# main.net
KiCad netlist of a schematic drawn in EAGLE
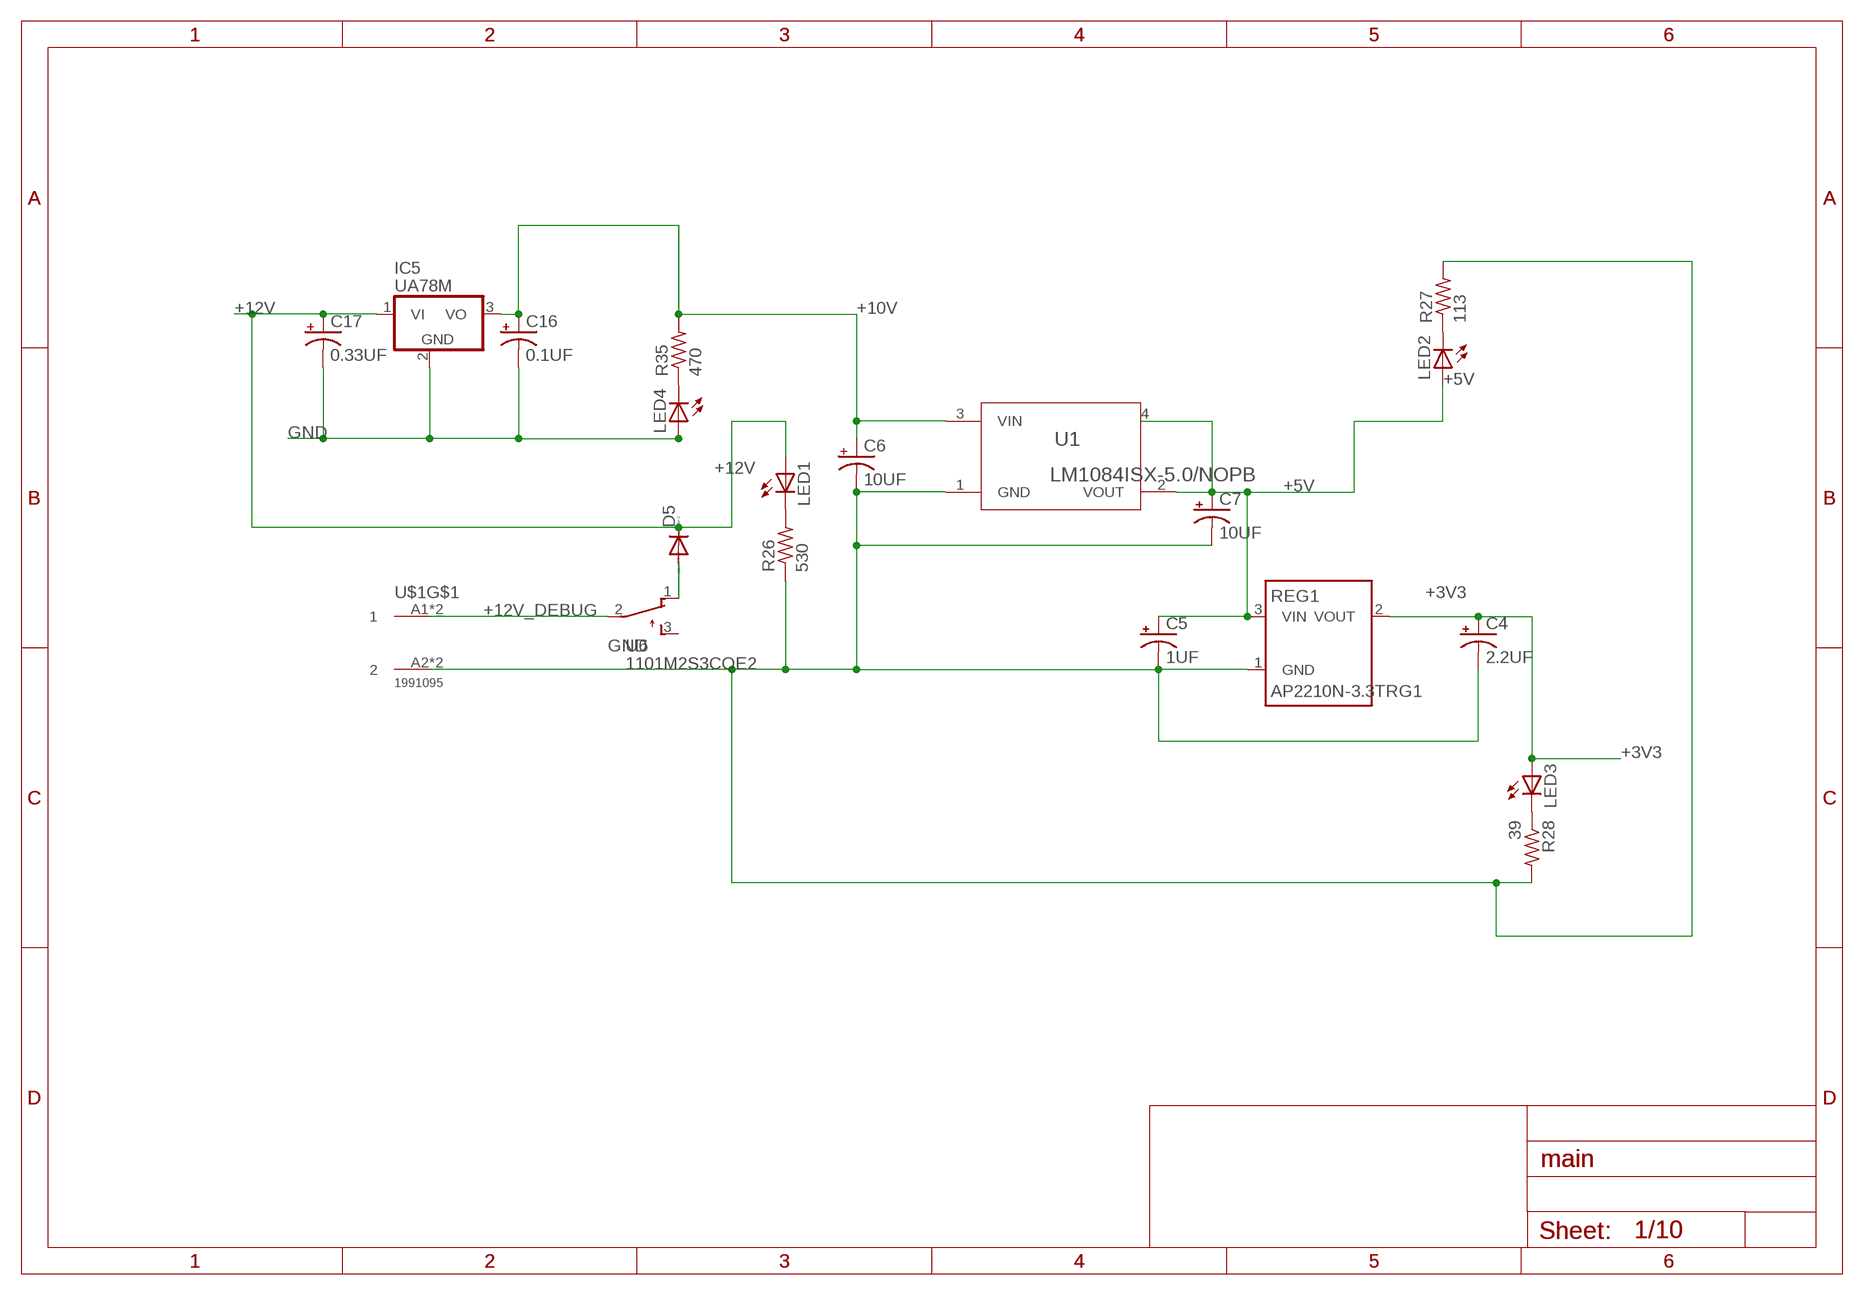
[diagram p0: schematic, sheet 1]
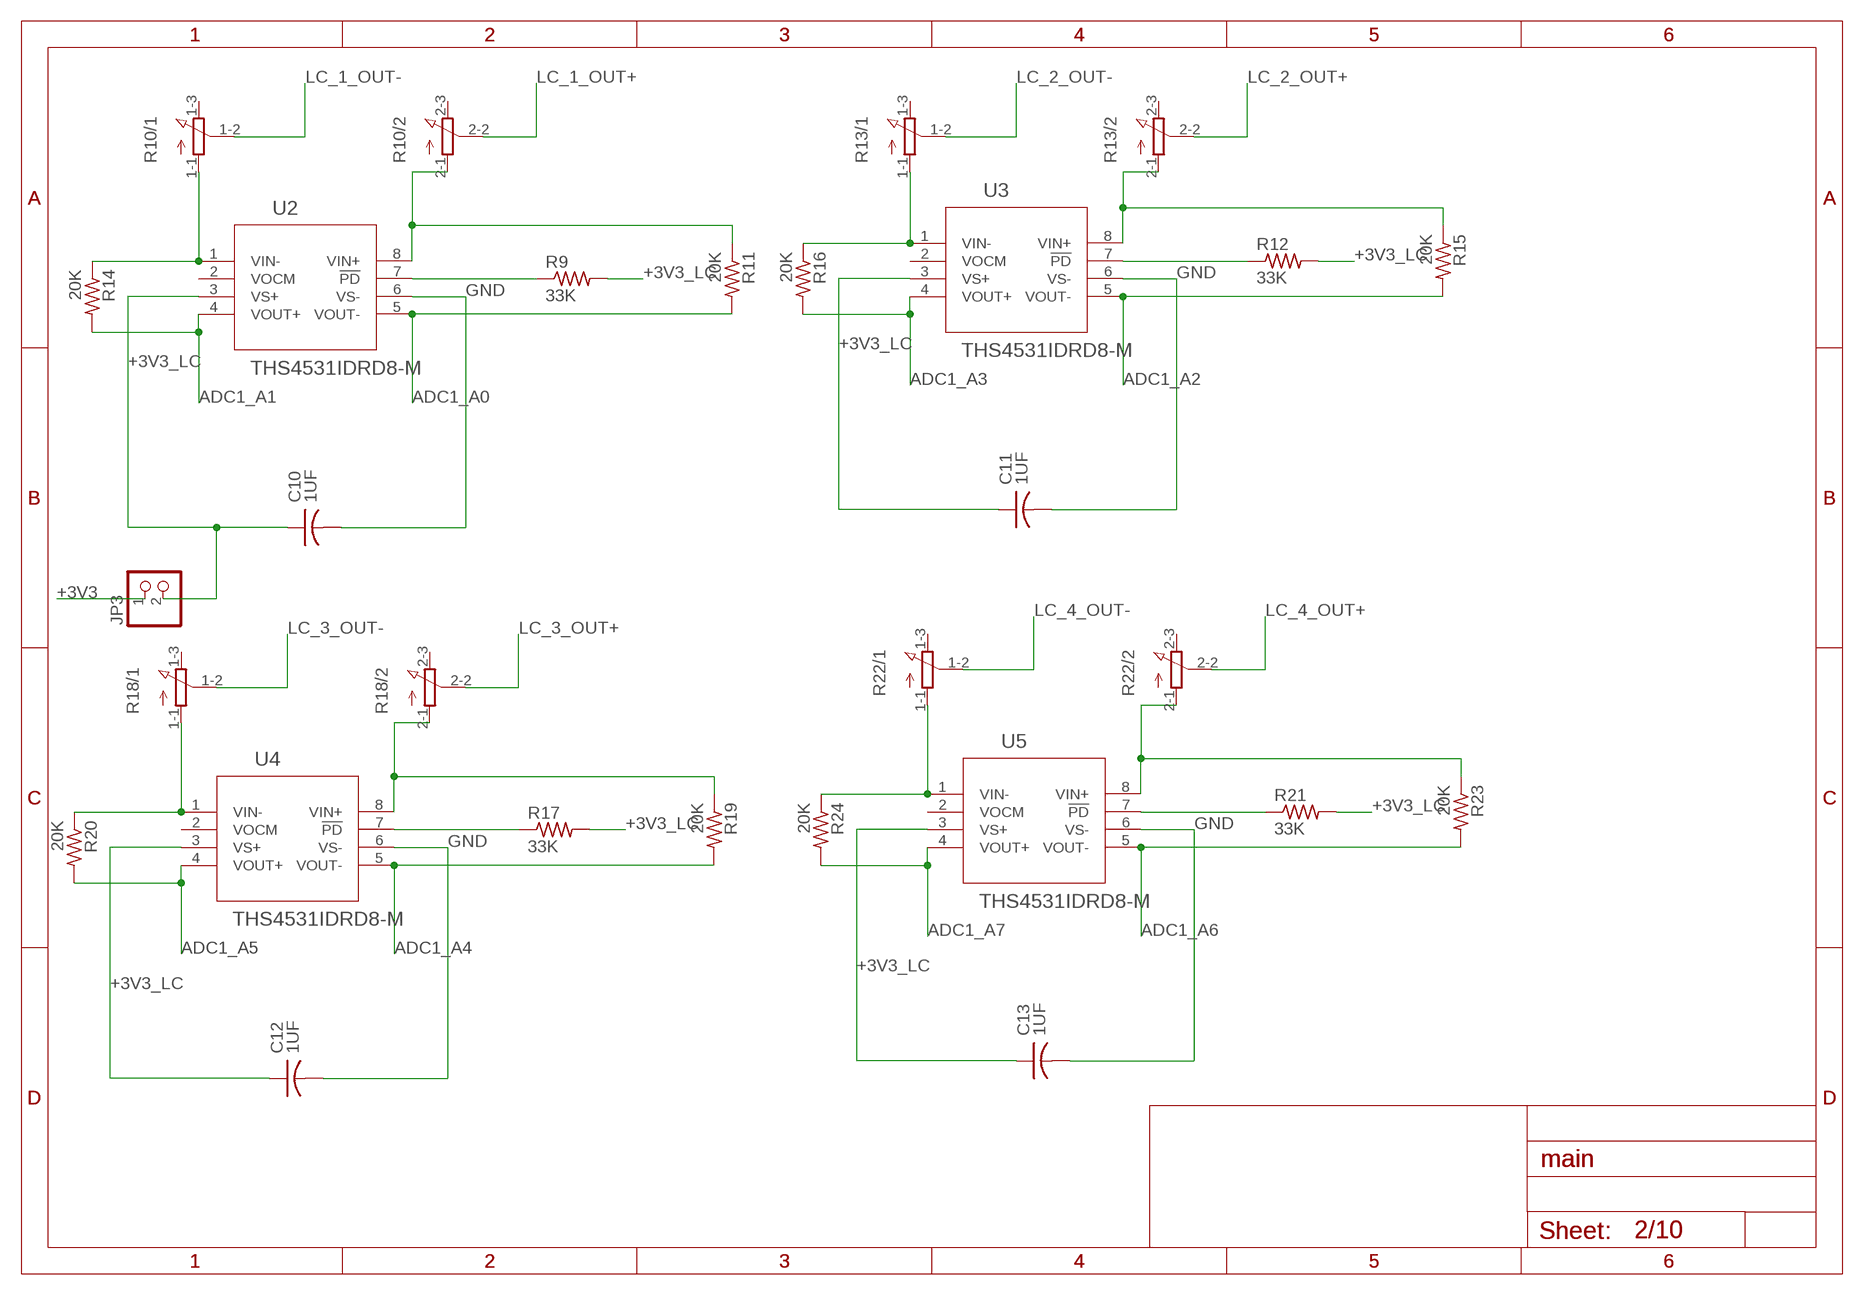
[diagram p1: schematic, sheet 2]
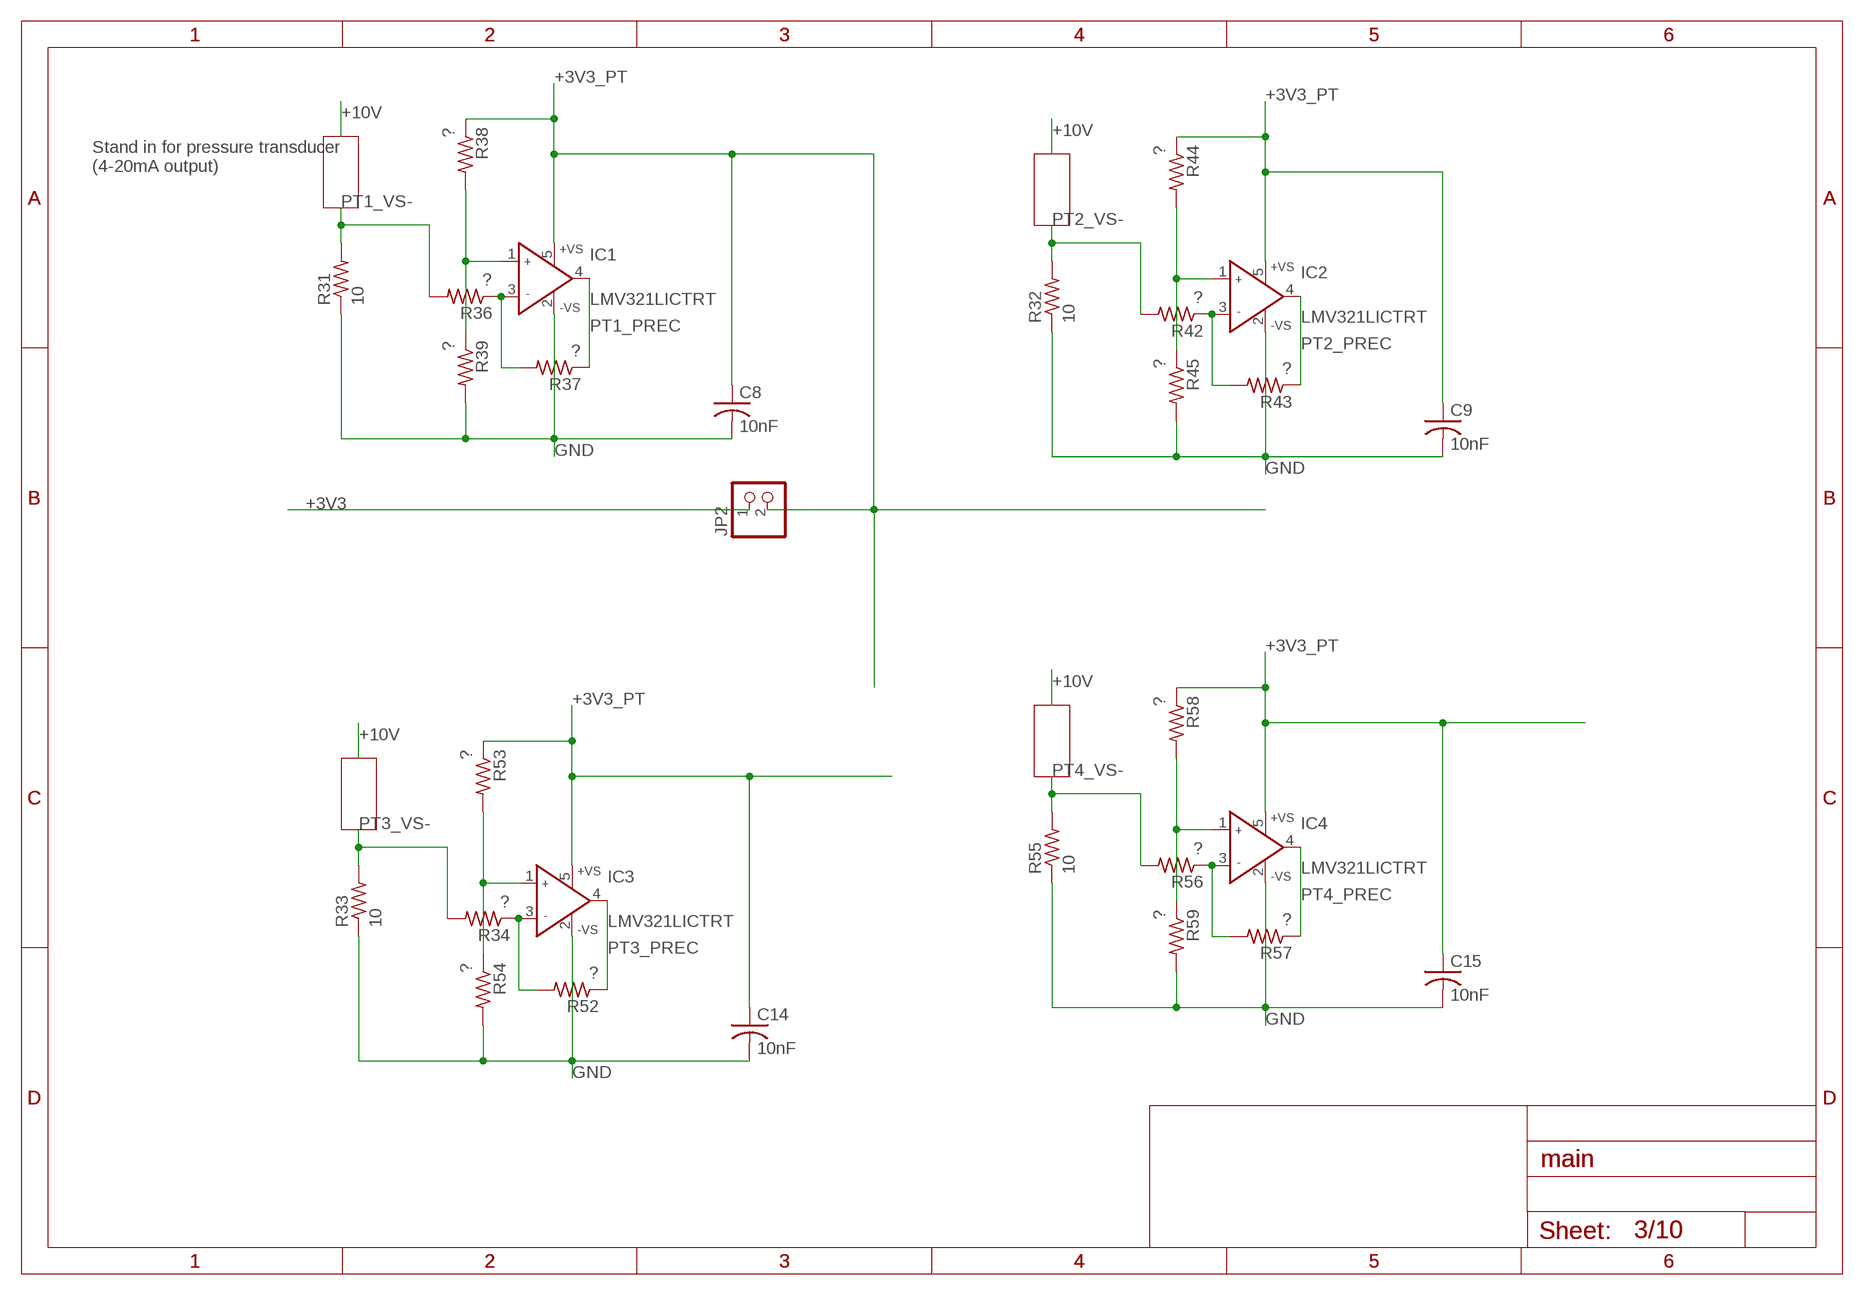
[diagram p2: schematic, sheet 3]
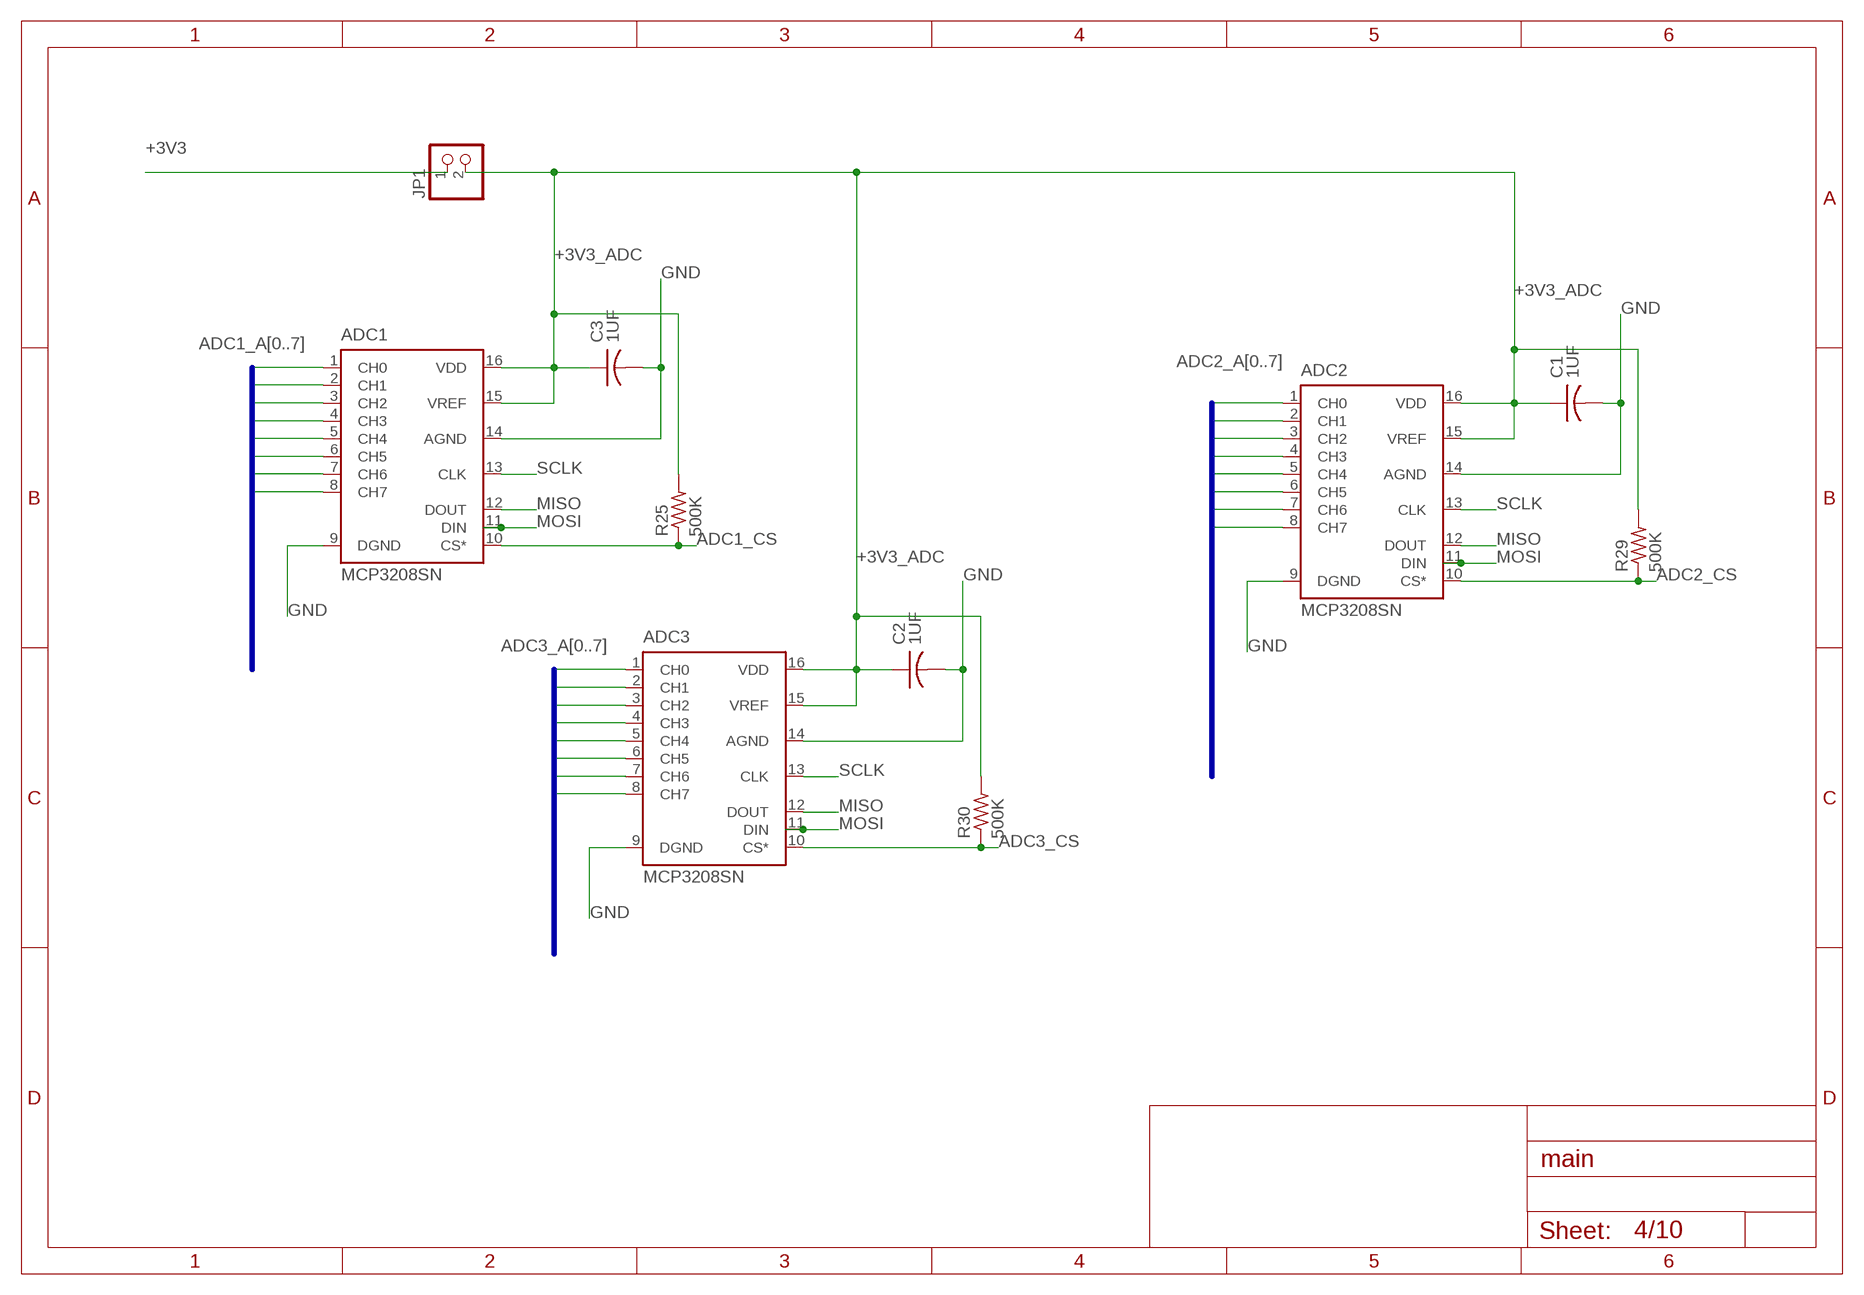
[diagram p3: schematic, sheet 4]
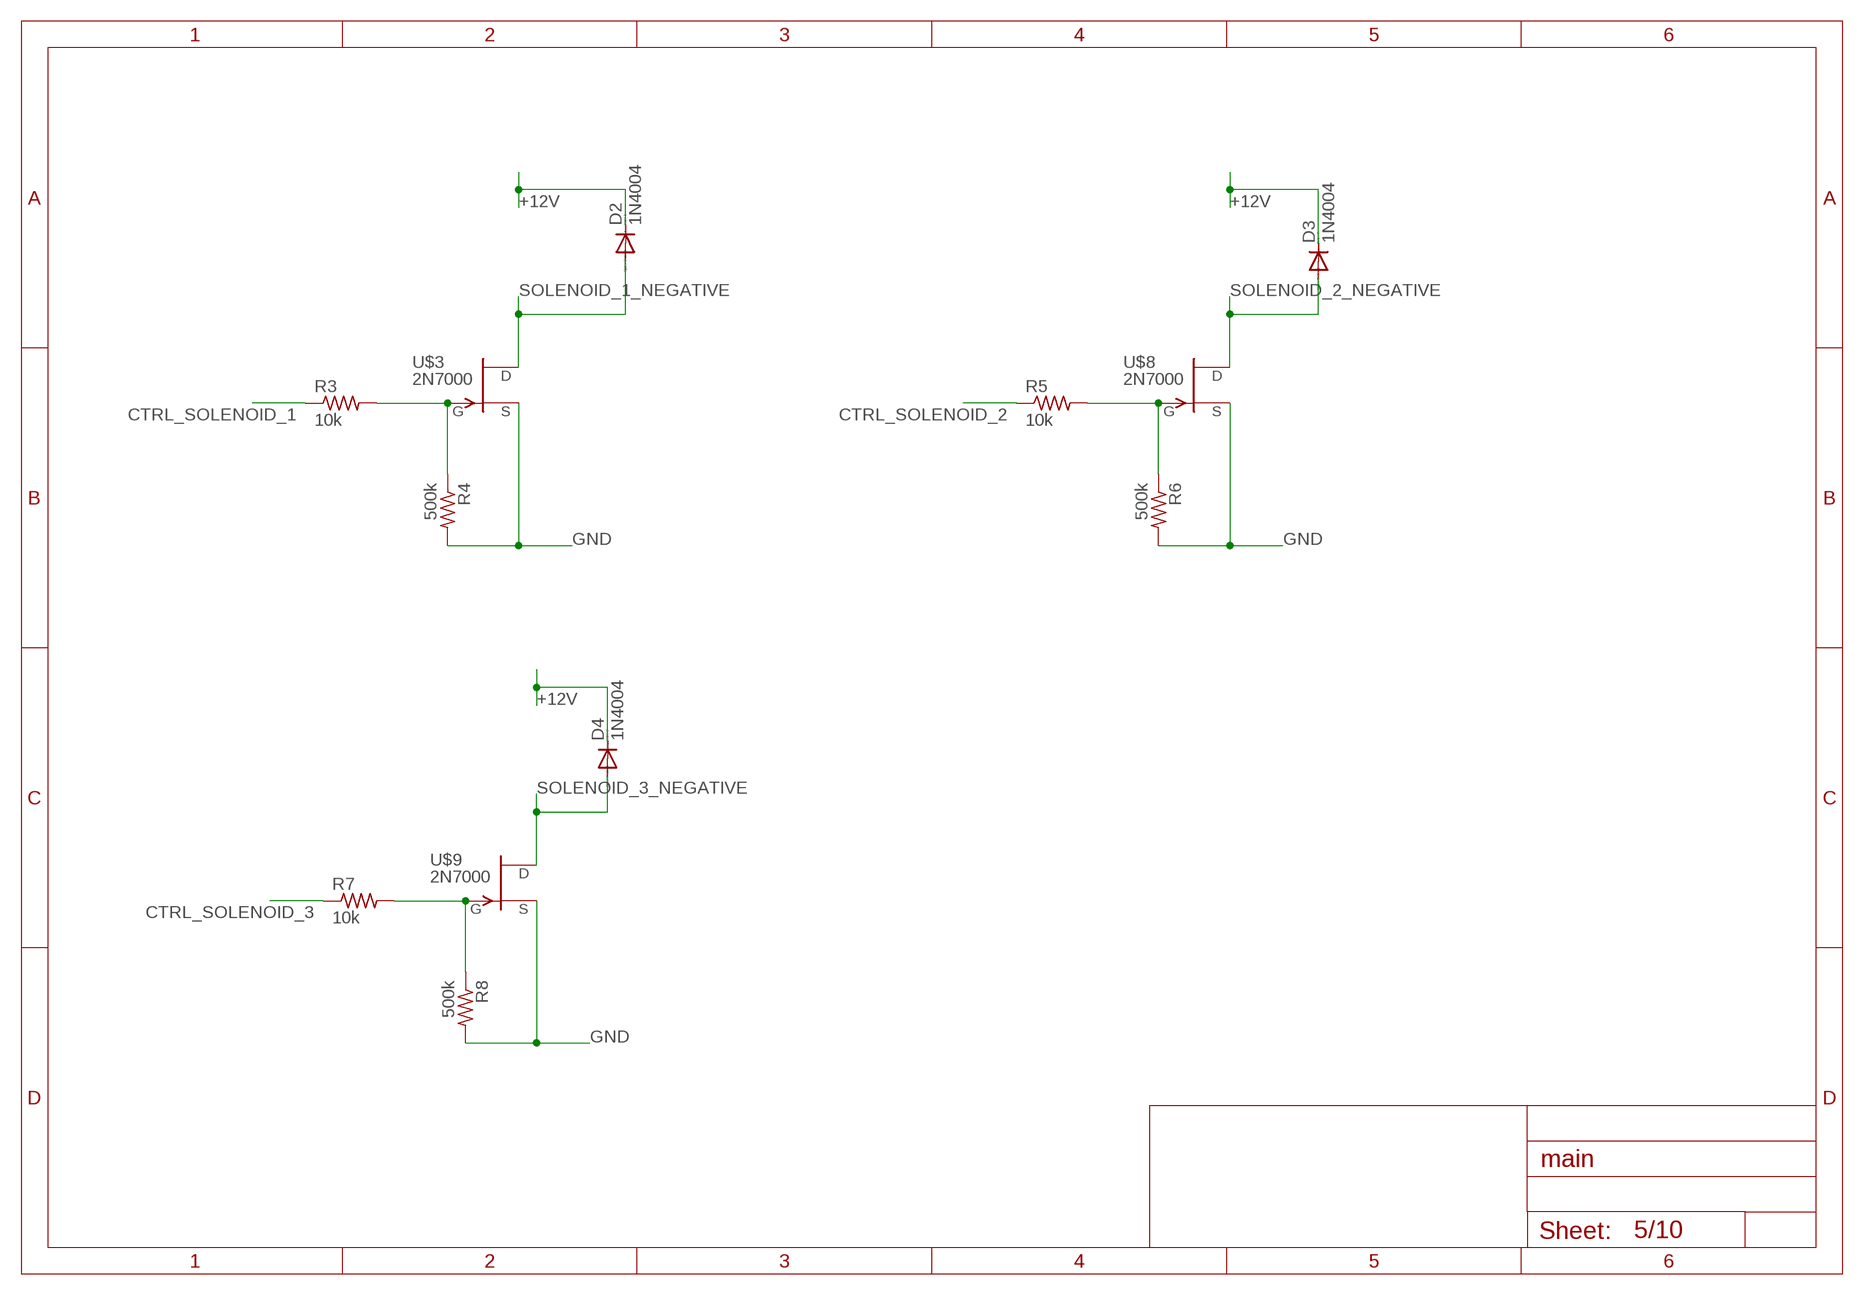
[diagram p4: schematic, sheet 5]
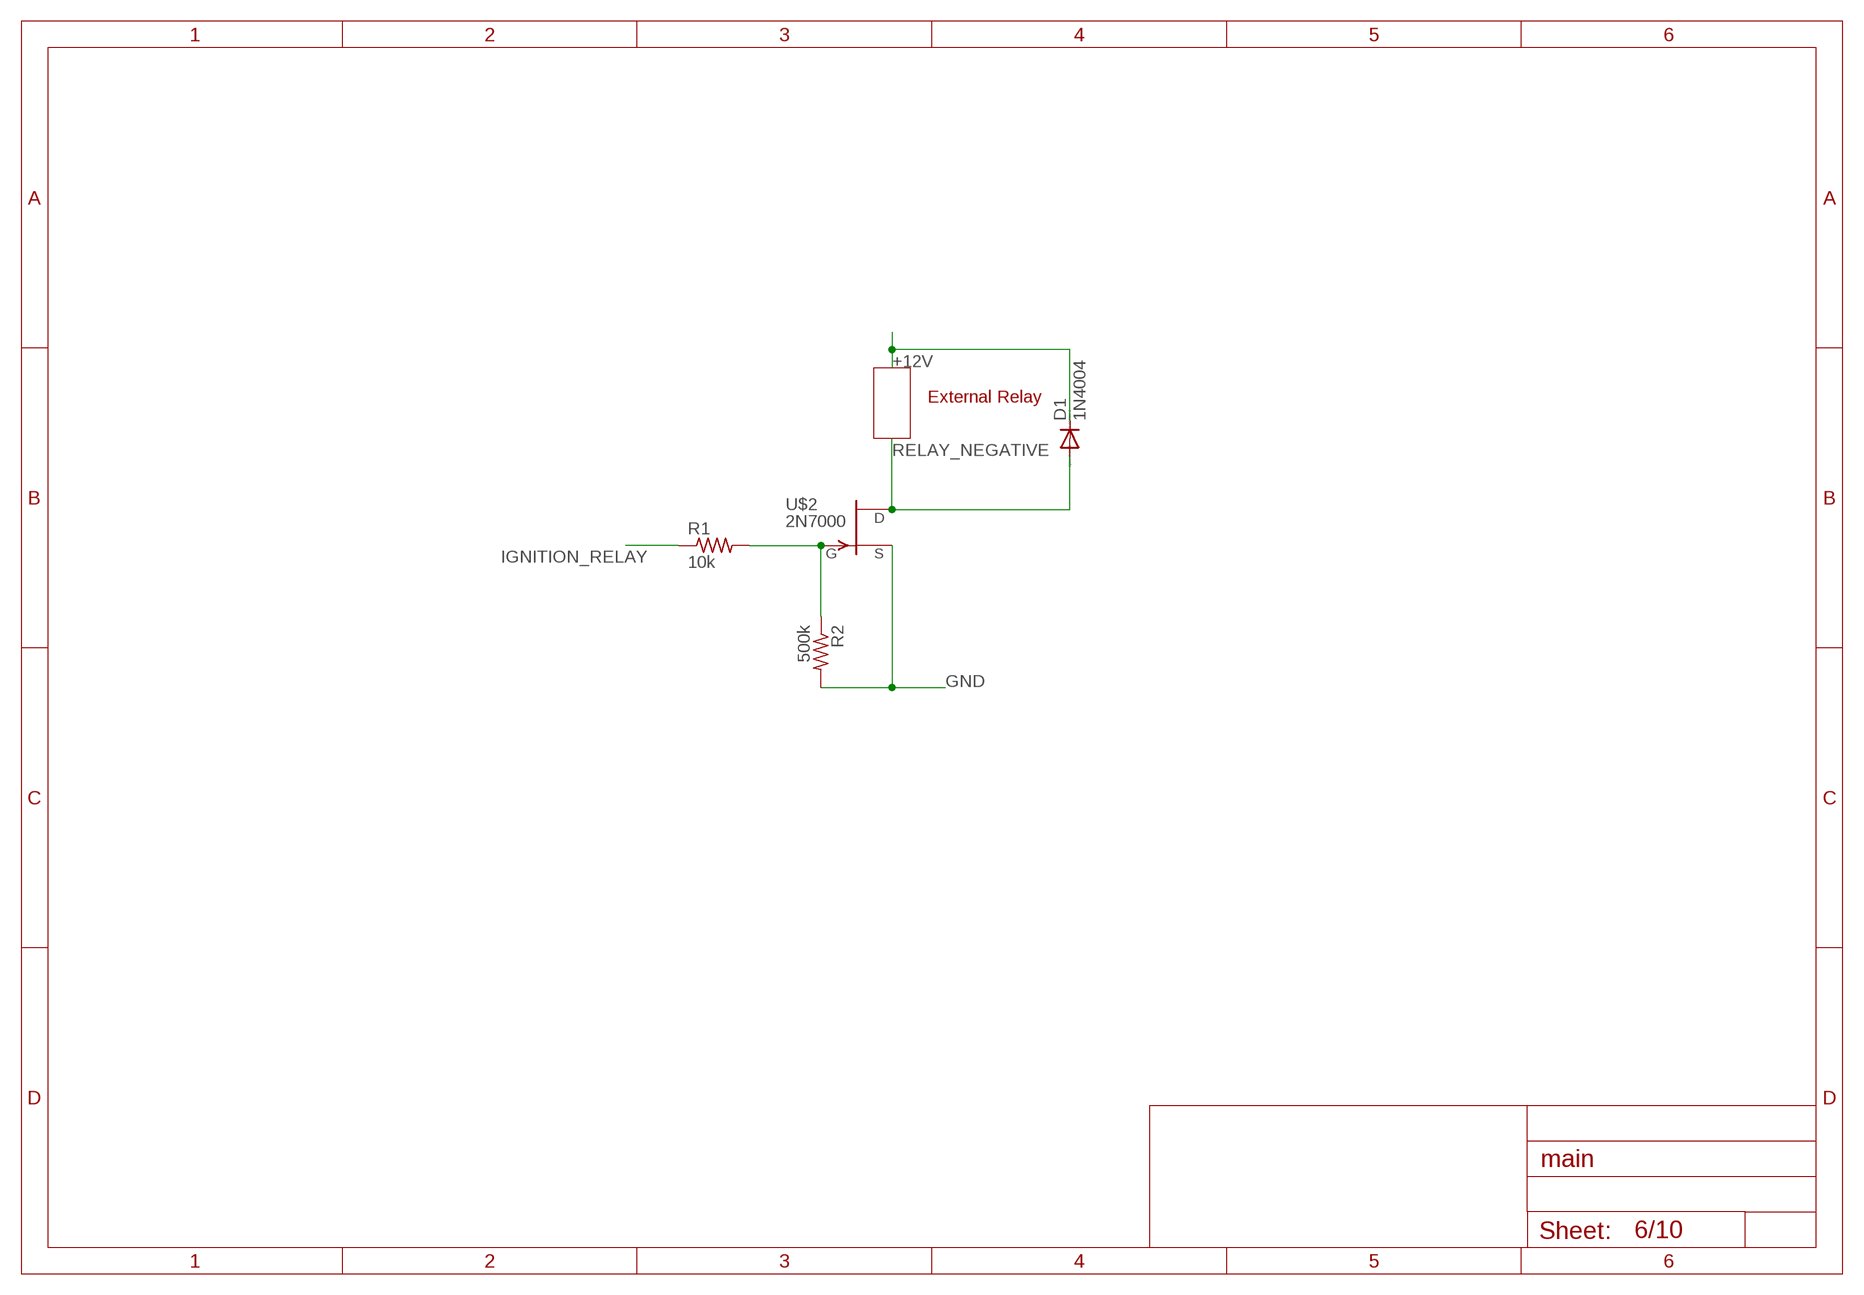
[diagram p5: schematic, sheet 6]
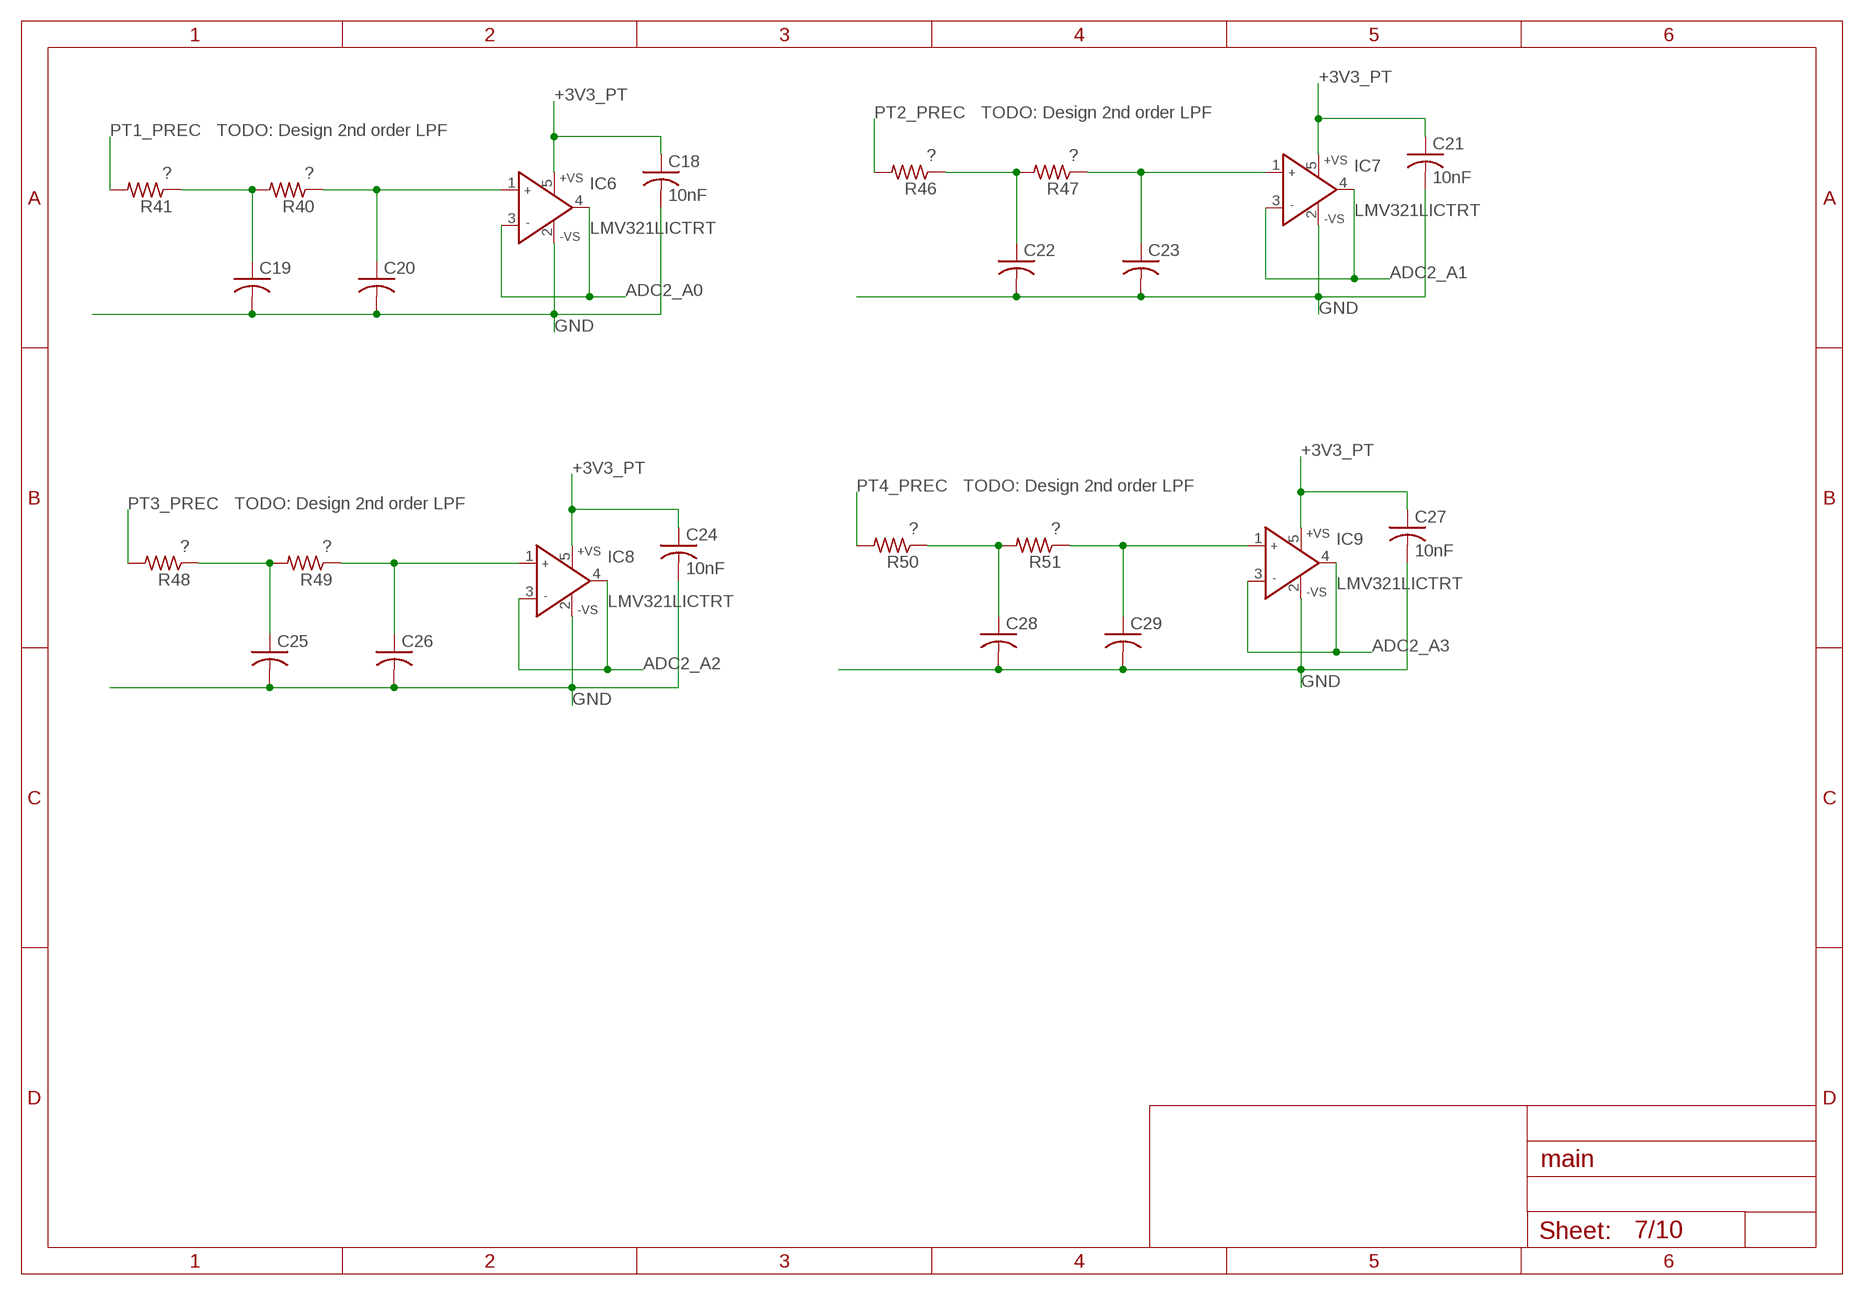
[diagram p6: schematic, sheet 7]
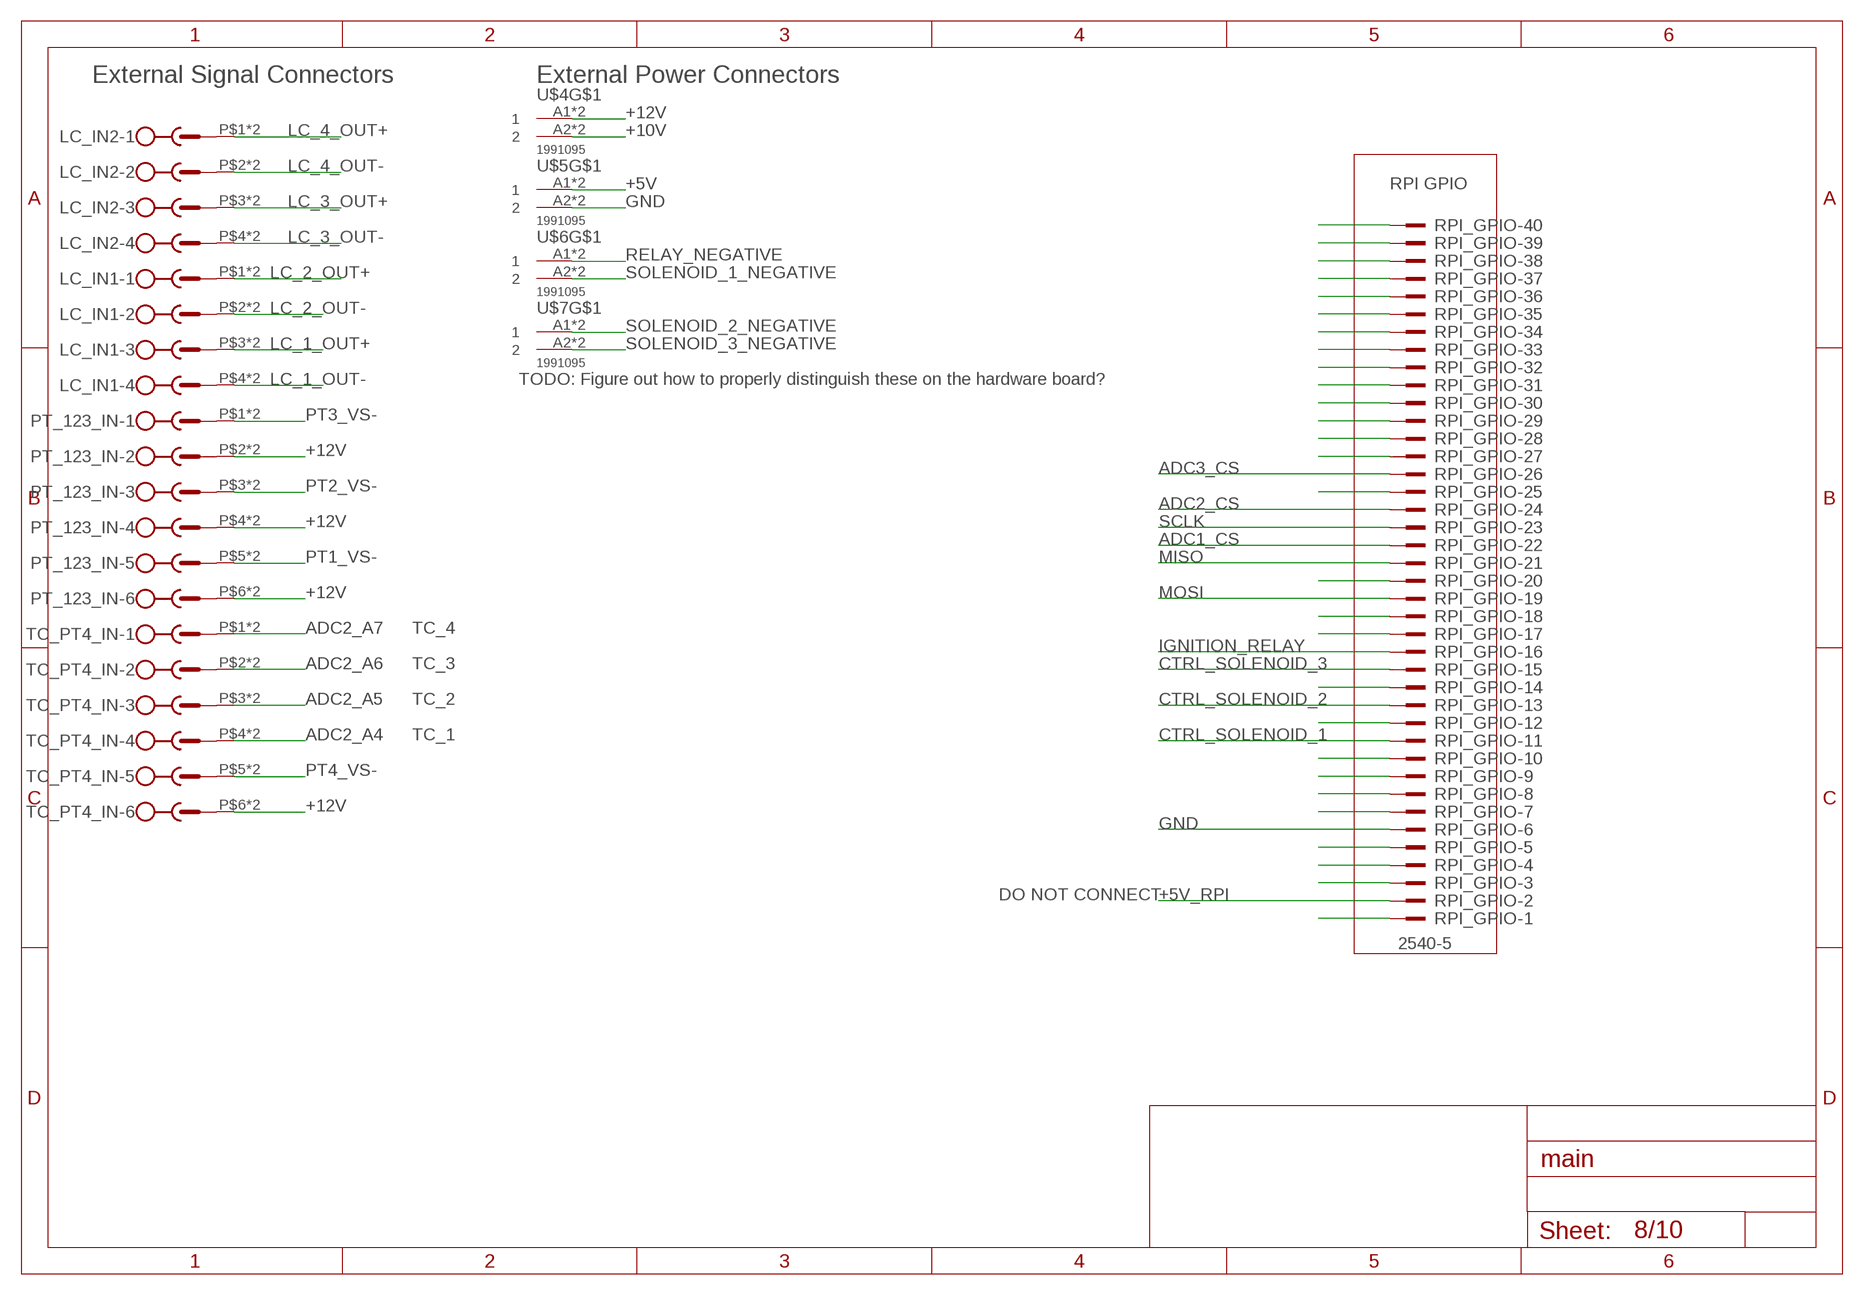
[diagram p7: schematic, sheet 8]
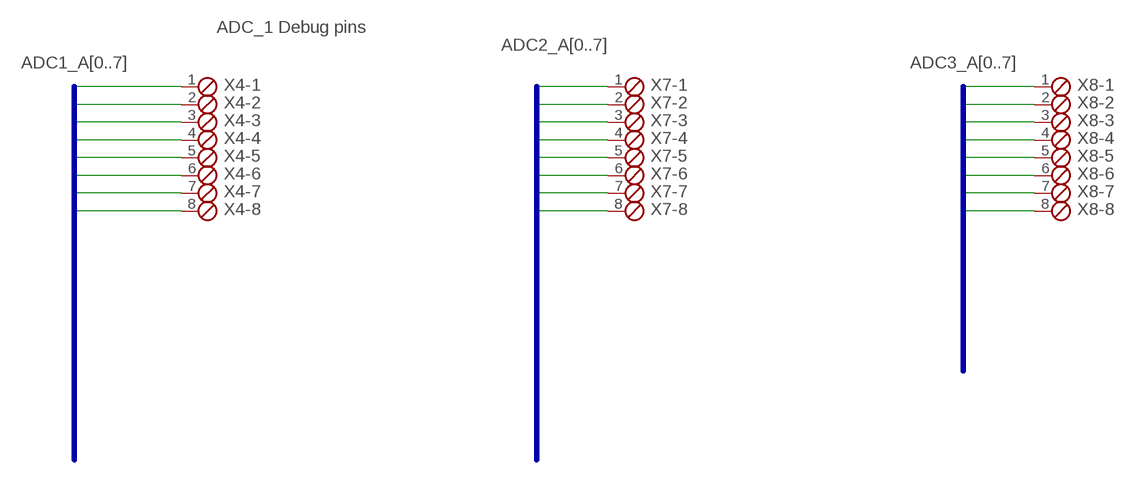
[diagram p8: schematic, sheet 9]

(export (version "E")
  (design (tool "Eeschema 10.0.6"))
  (components
    (comp (ref "C10")
      (value "1UF")
      (footprint "eagle-import:C0603")
      (libsource (lib "eagle-import") (part "C-USC0603"))
    )
    (comp (ref "C11")
      (value "1UF")
      (footprint "eagle-import:C0603")
      (libsource (lib "eagle-import") (part "C-USC0603"))
    )
    (comp (ref "C12")
      (value "1UF")
      (footprint "eagle-import:C0603")
      (libsource (lib "eagle-import") (part "C-USC0603"))
    )
    (comp (ref "C13")
      (value "1UF")
      (footprint "eagle-import:C0603")
      (libsource (lib "eagle-import") (part "C-USC0603"))
    )
    (comp (ref "JP3")
      (value "PINHD-1X2")
      (footprint "eagle-import:1X02")
      (libsource (lib "eagle-import") (part "PINHD-1X2"))
    )
    (comp (ref "R9")
      (value "33K")
      (footprint "eagle-import:R0603")
      (libsource (lib "eagle-import") (part "R-US_R0603"))
    )
    (comp (ref "R10")
      (value "PTD902")
      (footprint "eagle-import:PTD902")
      (libsource (lib "eagle-import") (part "PTD902"))
    )
    (comp (ref "R11")
      (value "20K")
      (footprint "eagle-import:R0603")
      (libsource (lib "eagle-import") (part "R-US_R0603"))
    )
    (comp (ref "R12")
      (value "33K")
      (footprint "eagle-import:R0603")
      (libsource (lib "eagle-import") (part "R-US_R0603"))
    )
    (comp (ref "R13")
      (value "PTD902")
      (footprint "eagle-import:PTD902")
      (libsource (lib "eagle-import") (part "PTD902"))
    )
    (comp (ref "R14")
      (value "20K")
      (footprint "eagle-import:R0603")
      (libsource (lib "eagle-import") (part "R-US_R0603"))
    )
    (comp (ref "R15")
      (value "20K")
      (footprint "eagle-import:R0603")
      (libsource (lib "eagle-import") (part "R-US_R0603"))
    )
    (comp (ref "R16")
      (value "20K")
      (footprint "eagle-import:R0603")
      (libsource (lib "eagle-import") (part "R-US_R0603"))
    )
    (comp (ref "R17")
      (value "33K")
      (footprint "eagle-import:R0603")
      (libsource (lib "eagle-import") (part "R-US_R0603"))
    )
    (comp (ref "R18")
      (value "PTD902")
      (footprint "eagle-import:PTD902")
      (libsource (lib "eagle-import") (part "PTD902"))
    )
    (comp (ref "R19")
      (value "20K")
      (footprint "eagle-import:R0603")
      (libsource (lib "eagle-import") (part "R-US_R0603"))
    )
    (comp (ref "R20")
      (value "20K")
      (footprint "eagle-import:R0603")
      (libsource (lib "eagle-import") (part "R-US_R0603"))
    )
    (comp (ref "R21")
      (value "33K")
      (footprint "eagle-import:R0603")
      (libsource (lib "eagle-import") (part "R-US_R0603"))
    )
    (comp (ref "R22")
      (value "PTD902")
      (footprint "eagle-import:PTD902")
      (libsource (lib "eagle-import") (part "PTD902"))
    )
    (comp (ref "R23")
      (value "20K")
      (footprint "eagle-import:R0603")
      (libsource (lib "eagle-import") (part "R-US_R0603"))
    )
    (comp (ref "R24")
      (value "20K")
      (footprint "eagle-import:R0603")
      (libsource (lib "eagle-import") (part "R-US_R0603"))
    )
    (comp (ref "U2")
      (value "THS4531IDRD8-M")
      (footprint "eagle-import:D8-M")
      (fields (field (name "MANUFACTURER_PART_NUMBER") "THS4531IDR"))
      (libsource (lib "eagle-import") (part "THS4531IDRD8-M"))
    )
    (comp (ref "U3")
      (value "THS4531IDRD8-M")
      (footprint "eagle-import:D8-M")
      (fields (field (name "MANUFACTURER_PART_NUMBER") "THS4531IDR"))
      (libsource (lib "eagle-import") (part "THS4531IDRD8-M"))
    )
    (comp (ref "U4")
      (value "THS4531IDRD8-M")
      (footprint "eagle-import:D8-M")
      (fields (field (name "MANUFACTURER_PART_NUMBER") "THS4531IDR"))
      (libsource (lib "eagle-import") (part "THS4531IDRD8-M"))
    )
    (comp (ref "U5")
      (value "THS4531IDRD8-M")
      (footprint "eagle-import:D8-M")
      (fields (field (name "MANUFACTURER_PART_NUMBER") "THS4531IDR"))
      (libsource (lib "eagle-import") (part "THS4531IDRD8-M"))
    )
    (comp (ref "D2")
      (value "1N4004")
      (footprint "eagle-import:DO41-10")
      (libsource (lib "eagle-import") (part "1N4004"))
    )
    (comp (ref "D3")
      (value "1N4004")
      (footprint "eagle-import:DO41-10")
      (libsource (lib "eagle-import") (part "1N4004"))
    )
    (comp (ref "D4")
      (value "1N4004")
      (footprint "eagle-import:DO41-10")
      (libsource (lib "eagle-import") (part "1N4004"))
    )
    (comp (ref "R3")
      (value "10k")
      (footprint "eagle-import:R0603")
      (libsource (lib "eagle-import") (part "R-US_R0603"))
    )
    (comp (ref "R4")
      (value "500k")
      (footprint "eagle-import:R0603")
      (libsource (lib "eagle-import") (part "R-US_R0603"))
    )
    (comp (ref "R5")
      (value "10k")
      (footprint "eagle-import:R0603")
      (libsource (lib "eagle-import") (part "R-US_R0603"))
    )
    (comp (ref "R6")
      (value "500k")
      (footprint "eagle-import:R0603")
      (libsource (lib "eagle-import") (part "R-US_R0603"))
    )
    (comp (ref "R7")
      (value "10k")
      (footprint "eagle-import:R0603")
      (libsource (lib "eagle-import") (part "R-US_R0603"))
    )
    (comp (ref "R8")
      (value "500k")
      (footprint "eagle-import:R0603")
      (libsource (lib "eagle-import") (part "R-US_R0603"))
    )
    (comp (ref "U$3")
      (value "2N7000")
      (footprint "eagle-import:SOT23")
      (libsource (lib "eagle-import") (part "2N7000"))
    )
    (comp (ref "U$8")
      (value "2N7000")
      (footprint "eagle-import:SOT23")
      (libsource (lib "eagle-import") (part "2N7000"))
    )
    (comp (ref "U$9")
      (value "2N7000")
      (footprint "eagle-import:SOT23")
      (libsource (lib "eagle-import") (part "2N7000"))
    )
    (comp (ref "D1")
      (value "1N4004")
      (footprint "eagle-import:DO41-10")
      (libsource (lib "eagle-import") (part "1N4004"))
    )
    (comp (ref "R1")
      (value "10k")
      (footprint "eagle-import:R0603")
      (libsource (lib "eagle-import") (part "R-US_R0603"))
    )
    (comp (ref "R2")
      (value "500k")
      (footprint "eagle-import:R0603")
      (libsource (lib "eagle-import") (part "R-US_R0603"))
    )
    (comp (ref "U$2")
      (value "2N7000")
      (footprint "eagle-import:SOT23")
      (libsource (lib "eagle-import") (part "2N7000"))
    )
    (comp (ref "X4")
      (value "MPT8")
      (footprint "eagle-import:8POL254")
      (libsource (lib "eagle-import") (part "MPT8"))
    )
    (comp (ref "X7")
      (value "MPT8")
      (footprint "eagle-import:8POL254")
      (libsource (lib "eagle-import") (part "MPT8"))
    )
    (comp (ref "X8")
      (value "MPT8")
      (footprint "eagle-import:8POL254")
      (libsource (lib "eagle-import") (part "MPT8"))
    )
    (comp (ref "LC_IN1")
      (value "1770908")
      (footprint "eagle-import:1770908")
      (libsource (lib "eagle-import") (part "1770908"))
    )
    (comp (ref "LC_IN2")
      (value "1770908")
      (footprint "eagle-import:1770908")
      (libsource (lib "eagle-import") (part "1770908"))
    )
    (comp (ref "PT_123_IN")
      (value "1770924")
      (footprint "eagle-import:1770924")
      (libsource (lib "eagle-import") (part "1770924"))
    )
    (comp (ref "RPI_GPIO")
      (value "2540-5")
      (footprint "eagle-import:PAK100_2500-5-40")
      (libsource (lib "eagle-import") (part "2540-5"))
    )
    (comp (ref "TC_PT4_IN")
      (value "1770924")
      (footprint "eagle-import:1770924")
      (libsource (lib "eagle-import") (part "1770924"))
    )
    (comp (ref "U$4")
      (value "1991095")
      (footprint "eagle-import:1991095")
      (libsource (lib "eagle-import") (part "1991095"))
    )
    (comp (ref "U$5")
      (value "1991095")
      (footprint "eagle-import:1991095")
      (libsource (lib "eagle-import") (part "1991095"))
    )
    (comp (ref "U$6")
      (value "1991095")
      (footprint "eagle-import:1991095")
      (libsource (lib "eagle-import") (part "1991095"))
    )
    (comp (ref "U$7")
      (value "1991095")
      (footprint "eagle-import:1991095")
      (libsource (lib "eagle-import") (part "1991095"))
    )
    (comp (ref "C18")
      (value "10nF")
      (footprint "eagle-import:C0402K")
      (libsource (lib "eagle-import") (part "C-USC0402K"))
    )
    (comp (ref "C19")
      (value "C-US025-025X050")
      (footprint "eagle-import:C025-025X050")
      (libsource (lib "eagle-import") (part "C-US025-025X050"))
    )
    (comp (ref "C20")
      (value "C-US025-025X050")
      (footprint "eagle-import:C025-025X050")
      (libsource (lib "eagle-import") (part "C-US025-025X050"))
    )
    (comp (ref "C21")
      (value "10nF")
      (footprint "eagle-import:C0402K")
      (libsource (lib "eagle-import") (part "C-USC0402K"))
    )
    (comp (ref "C22")
      (value "C-US025-025X050")
      (footprint "eagle-import:C025-025X050")
      (libsource (lib "eagle-import") (part "C-US025-025X050"))
    )
    (comp (ref "C23")
      (value "C-US025-025X050")
      (footprint "eagle-import:C025-025X050")
      (libsource (lib "eagle-import") (part "C-US025-025X050"))
    )
    (comp (ref "C24")
      (value "10nF")
      (footprint "eagle-import:C0402K")
      (libsource (lib "eagle-import") (part "C-USC0402K"))
    )
    (comp (ref "C25")
      (value "C-US025-025X050")
      (footprint "eagle-import:C025-025X050")
      (libsource (lib "eagle-import") (part "C-US025-025X050"))
    )
    (comp (ref "C26")
      (value "C-US025-025X050")
      (footprint "eagle-import:C025-025X050")
      (libsource (lib "eagle-import") (part "C-US025-025X050"))
    )
    (comp (ref "C27")
      (value "10nF")
      (footprint "eagle-import:C0402K")
      (libsource (lib "eagle-import") (part "C-USC0402K"))
    )
    (comp (ref "C28")
      (value "C-US025-025X050")
      (footprint "eagle-import:C025-025X050")
      (libsource (lib "eagle-import") (part "C-US025-025X050"))
    )
    (comp (ref "C29")
      (value "C-US025-025X050")
      (footprint "eagle-import:C025-025X050")
      (libsource (lib "eagle-import") (part "C-US025-025X050"))
    )
    (comp (ref "IC6")
      (value "LMV321LICTRT")
      (footprint "eagle-import:SOT23-5")
      (fields (field (name "MF") "ALTERA CORPORATION") (field (name "MPN") "AD8065ARTZ-REEL7"))
      (libsource (lib "eagle-import") (part "LMV321LICTRT"))
    )
    (comp (ref "IC7")
      (value "LMV321LICTRT")
      (footprint "eagle-import:SOT23-5")
      (fields (field (name "MF") "ALTERA CORPORATION") (field (name "MPN") "AD8065ARTZ-REEL7"))
      (libsource (lib "eagle-import") (part "LMV321LICTRT"))
    )
    (comp (ref "IC8")
      (value "LMV321LICTRT")
      (footprint "eagle-import:SOT23-5")
      (fields (field (name "MF") "ALTERA CORPORATION") (field (name "MPN") "AD8065ARTZ-REEL7"))
      (libsource (lib "eagle-import") (part "LMV321LICTRT"))
    )
    (comp (ref "IC9")
      (value "LMV321LICTRT")
      (footprint "eagle-import:SOT23-5")
      (fields (field (name "MF") "ALTERA CORPORATION") (field (name "MPN") "AD8065ARTZ-REEL7"))
      (libsource (lib "eagle-import") (part "LMV321LICTRT"))
    )
    (comp (ref "R40")
      (value "?")
      (footprint "eagle-import:0204_7")
      (libsource (lib "eagle-import") (part "R-US_0204/7"))
    )
    (comp (ref "R41")
      (value "?")
      (footprint "eagle-import:0204_7")
      (libsource (lib "eagle-import") (part "R-US_0204/7"))
    )
    (comp (ref "R46")
      (value "?")
      (footprint "eagle-import:0204_7")
      (libsource (lib "eagle-import") (part "R-US_0204/7"))
    )
    (comp (ref "R47")
      (value "?")
      (footprint "eagle-import:0204_7")
      (libsource (lib "eagle-import") (part "R-US_0204/7"))
    )
    (comp (ref "R48")
      (value "?")
      (footprint "eagle-import:0204_7")
      (libsource (lib "eagle-import") (part "R-US_0204/7"))
    )
    (comp (ref "R49")
      (value "?")
      (footprint "eagle-import:0204_7")
      (libsource (lib "eagle-import") (part "R-US_0204/7"))
    )
    (comp (ref "R50")
      (value "?")
      (footprint "eagle-import:0204_7")
      (libsource (lib "eagle-import") (part "R-US_0204/7"))
    )
    (comp (ref "R51")
      (value "?")
      (footprint "eagle-import:0204_7")
      (libsource (lib "eagle-import") (part "R-US_0204/7"))
    )
    (comp (ref "C8")
      (value "10nF")
      (footprint "eagle-import:C0402K")
      (libsource (lib "eagle-import") (part "C-USC0402K"))
    )
    (comp (ref "C9")
      (value "10nF")
      (footprint "eagle-import:C0402K")
      (libsource (lib "eagle-import") (part "C-USC0402K"))
    )
    (comp (ref "C14")
      (value "10nF")
      (footprint "eagle-import:C0402K")
      (libsource (lib "eagle-import") (part "C-USC0402K"))
    )
    (comp (ref "C15")
      (value "10nF")
      (footprint "eagle-import:C0402K")
      (libsource (lib "eagle-import") (part "C-USC0402K"))
    )
    (comp (ref "IC1")
      (value "LMV321LICTRT")
      (footprint "eagle-import:SOT23-5")
      (fields (field (name "MF") "ALTERA CORPORATION") (field (name "MPN") "AD8065ARTZ-REEL7"))
      (libsource (lib "eagle-import") (part "LMV321LICTRT"))
    )
    (comp (ref "IC2")
      (value "LMV321LICTRT")
      (footprint "eagle-import:SOT23-5")
      (fields (field (name "MF") "ALTERA CORPORATION") (field (name "MPN") "AD8065ARTZ-REEL7"))
      (libsource (lib "eagle-import") (part "LMV321LICTRT"))
    )
    (comp (ref "IC3")
      (value "LMV321LICTRT")
      (footprint "eagle-import:SOT23-5")
      (fields (field (name "MF") "ALTERA CORPORATION") (field (name "MPN") "AD8065ARTZ-REEL7"))
      (libsource (lib "eagle-import") (part "LMV321LICTRT"))
    )
    (comp (ref "IC4")
      (value "LMV321LICTRT")
      (footprint "eagle-import:SOT23-5")
      (fields (field (name "MF") "ALTERA CORPORATION") (field (name "MPN") "AD8065ARTZ-REEL7"))
      (libsource (lib "eagle-import") (part "LMV321LICTRT"))
    )
    (comp (ref "JP2")
      (value "PINHD-1X2")
      (footprint "eagle-import:1X02")
      (libsource (lib "eagle-import") (part "PINHD-1X2"))
    )
    (comp (ref "R31")
      (value "10")
      (footprint "eagle-import:R0603")
      (libsource (lib "eagle-import") (part "R-US_R0603"))
    )
    (comp (ref "R32")
      (value "10")
      (footprint "eagle-import:R0603")
      (libsource (lib "eagle-import") (part "R-US_R0603"))
    )
    (comp (ref "R33")
      (value "10")
      (footprint "eagle-import:R0603")
      (libsource (lib "eagle-import") (part "R-US_R0603"))
    )
    (comp (ref "R34")
      (value "?")
      (footprint "eagle-import:0204_7")
      (libsource (lib "eagle-import") (part "R-US_0204/7"))
    )
    (comp (ref "R36")
      (value "?")
      (footprint "eagle-import:0204_7")
      (libsource (lib "eagle-import") (part "R-US_0204/7"))
    )
    (comp (ref "R37")
      (value "?")
      (footprint "eagle-import:0204_7")
      (libsource (lib "eagle-import") (part "R-US_0204/7"))
    )
    (comp (ref "R38")
      (value "?")
      (footprint "eagle-import:0204_7")
      (libsource (lib "eagle-import") (part "R-US_0204/7"))
    )
    (comp (ref "R39")
      (value "?")
      (footprint "eagle-import:0204_7")
      (libsource (lib "eagle-import") (part "R-US_0204/7"))
    )
    (comp (ref "R42")
      (value "?")
      (footprint "eagle-import:0204_7")
      (libsource (lib "eagle-import") (part "R-US_0204/7"))
    )
    (comp (ref "R43")
      (value "?")
      (footprint "eagle-import:0204_7")
      (libsource (lib "eagle-import") (part "R-US_0204/7"))
    )
    (comp (ref "R44")
      (value "?")
      (footprint "eagle-import:0204_7")
      (libsource (lib "eagle-import") (part "R-US_0204/7"))
    )
    (comp (ref "R45")
      (value "?")
      (footprint "eagle-import:0204_7")
      (libsource (lib "eagle-import") (part "R-US_0204/7"))
    )
    (comp (ref "R52")
      (value "?")
      (footprint "eagle-import:0204_7")
      (libsource (lib "eagle-import") (part "R-US_0204/7"))
    )
    (comp (ref "R53")
      (value "?")
      (footprint "eagle-import:0204_7")
      (libsource (lib "eagle-import") (part "R-US_0204/7"))
    )
    (comp (ref "R54")
      (value "?")
      (footprint "eagle-import:0204_7")
      (libsource (lib "eagle-import") (part "R-US_0204/7"))
    )
    (comp (ref "R55")
      (value "10")
      (footprint "eagle-import:R0603")
      (libsource (lib "eagle-import") (part "R-US_R0603"))
    )
    (comp (ref "R56")
      (value "?")
      (footprint "eagle-import:0204_7")
      (libsource (lib "eagle-import") (part "R-US_0204/7"))
    )
    (comp (ref "R57")
      (value "?")
      (footprint "eagle-import:0204_7")
      (libsource (lib "eagle-import") (part "R-US_0204/7"))
    )
    (comp (ref "R58")
      (value "?")
      (footprint "eagle-import:0204_7")
      (libsource (lib "eagle-import") (part "R-US_0204/7"))
    )
    (comp (ref "R59")
      (value "?")
      (footprint "eagle-import:0204_7")
      (libsource (lib "eagle-import") (part "R-US_0204/7"))
    )
    (comp (ref "ADC1")
      (value "MCP3208SN")
      (footprint "eagle-import:SO-16")
      (fields (field (name "MF") "MICROCHIP") (field (name "MPN") "MCP3202-CI/SN"))
      (libsource (lib "eagle-import") (part "MCP3208SN"))
    )
    (comp (ref "ADC2")
      (value "MCP3208SN")
      (footprint "eagle-import:SO-16")
      (fields (field (name "MF") "MICROCHIP") (field (name "MPN") "MCP3202-CI/SN"))
      (libsource (lib "eagle-import") (part "MCP3208SN"))
    )
    (comp (ref "ADC3")
      (value "MCP3208SN")
      (footprint "eagle-import:SO-16")
      (fields (field (name "MF") "MICROCHIP") (field (name "MPN") "MCP3202-CI/SN"))
      (libsource (lib "eagle-import") (part "MCP3208SN"))
    )
    (comp (ref "C1")
      (value "1UF")
      (footprint "eagle-import:C0603")
      (libsource (lib "eagle-import") (part "C-USC0603"))
    )
    (comp (ref "C2")
      (value "1UF")
      (footprint "eagle-import:C0603")
      (libsource (lib "eagle-import") (part "C-USC0603"))
    )
    (comp (ref "C3")
      (value "1UF")
      (footprint "eagle-import:C0603")
      (libsource (lib "eagle-import") (part "C-USC0603"))
    )
    (comp (ref "JP1")
      (value "PINHD-1X2")
      (footprint "eagle-import:1X02")
      (libsource (lib "eagle-import") (part "PINHD-1X2"))
    )
    (comp (ref "R25")
      (value "500K")
      (footprint "eagle-import:R0603")
      (libsource (lib "eagle-import") (part "R-US_R0603"))
    )
    (comp (ref "R29")
      (value "500K")
      (footprint "eagle-import:R0603")
      (libsource (lib "eagle-import") (part "R-US_R0603"))
    )
    (comp (ref "R30")
      (value "500K")
      (footprint "eagle-import:R0603")
      (libsource (lib "eagle-import") (part "R-US_R0603"))
    )
    (comp (ref "C4")
      (value "2.2UF")
      (footprint "eagle-import:E2,5-5")
      (libsource (lib "eagle-import") (part "CPOL-USE2.5-5"))
    )
    (comp (ref "C5")
      (value "1UF")
      (footprint "eagle-import:E2,5-5")
      (libsource (lib "eagle-import") (part "CPOL-USE2.5-5"))
    )
    (comp (ref "C6")
      (value "10UF")
      (footprint "eagle-import:E2,5-5")
      (libsource (lib "eagle-import") (part "CPOL-USE2.5-5"))
    )
    (comp (ref "C7")
      (value "10UF")
      (footprint "eagle-import:E2,5-5")
      (libsource (lib "eagle-import") (part "CPOL-USE2.5-5"))
    )
    (comp (ref "C16")
      (value "0.1UF")
      (footprint "eagle-import:E2,5-5")
      (libsource (lib "eagle-import") (part "CPOL-USE2.5-5"))
    )
    (comp (ref "C17")
      (value "0.33UF")
      (footprint "eagle-import:E2,5-5")
      (libsource (lib "eagle-import") (part "CPOL-USE2.5-5"))
    )
    (comp (ref "D5")
      (value "DIODE-DO201-15")
      (footprint "eagle-import:DO201-15")
      (libsource (lib "eagle-import") (part "DIODE-DO201-15"))
    )
    (comp (ref "IC5")
      (value "UA78M")
      (footprint "eagle-import:TO220S")
      (libsource (lib "eagle-import") (part "UA78M"))
    )
    (comp (ref "LED1")
      (value "LED5MM")
      (footprint "eagle-import:LED5MM")
      (libsource (lib "eagle-import") (part "LED5MM"))
    )
    (comp (ref "LED2")
      (value "LED5MM")
      (footprint "eagle-import:LED5MM")
      (libsource (lib "eagle-import") (part "LED5MM"))
    )
    (comp (ref "LED3")
      (value "LED5MM")
      (footprint "eagle-import:LED5MM")
      (libsource (lib "eagle-import") (part "LED5MM"))
    )
    (comp (ref "LED4")
      (value "LED5MM")
      (footprint "eagle-import:LED5MM")
      (libsource (lib "eagle-import") (part "LED5MM"))
    )
    (comp (ref "R26")
      (value "530")
      (footprint "eagle-import:R0603")
      (libsource (lib "eagle-import") (part "resistor_348_R-US_R0603"))
    )
    (comp (ref "R27")
      (value "113")
      (footprint "eagle-import:R0603")
      (libsource (lib "eagle-import") (part "resistor_348_R-US_R0603"))
    )
    (comp (ref "R28")
      (value "39")
      (footprint "eagle-import:R0603")
      (libsource (lib "eagle-import") (part "resistor_348_R-US_R0603"))
    )
    (comp (ref "R35")
      (value "470")
      (footprint "eagle-import:R0603")
      (libsource (lib "eagle-import") (part "resistor_348_R-US_R0603"))
    )
    (comp (ref "REG1")
      (value "AP2210N-3.3TRG1")
      (footprint "eagle-import:SOT23")
      (libsource (lib "eagle-import") (part "AP2210N-3.3TRG1"))
    )
    (comp (ref "U$1")
      (value "1991095")
      (footprint "eagle-import:1991095")
      (libsource (lib "eagle-import") (part "1991095"))
    )
    (comp (ref "U1")
      (value "LM1084ISX-5.0/NOPB")
      (footprint "eagle-import:TS3B")
      (fields (field (name "MANUFACTURER_PART_NUMBER") "LM1084ISX5.0NOPB"))
      (libsource (lib "eagle-import") (part "LM1084ISX-5.0/NOPB"))
    )
    (comp (ref "U6")
      (value "1101M2S3CQE2")
      (footprint "eagle-import:1101M2S3CQE2")
      (fields (field (name "COPYRIGHT") "Copyright (C) 2015 Accelerated Designs. All rights reserved"))
      (libsource (lib "eagle-import") (part "1101M2S3CQE2"))
    )
  )
  (nets
    (net (code "1") (name "+3V3") (class "Default")
      (node (ref "C4") (pin "+") (pinfunction "+_+") (pintype "passive"))
      (node (ref "JP1") (pin "1") (pinfunction "1_1") (pintype "passive"))
      (node (ref "JP2") (pin "1") (pinfunction "1_1") (pintype "passive"))
      (node (ref "JP3") (pin "1") (pinfunction "1_1") (pintype "passive"))
      (node (ref "LED3") (pin "A") (pinfunction "A_A") (pintype "passive"))
      (node (ref "REG1") (pin "2") (pinfunction "VOUT_2") (pintype "passive"))
    )
    (net (code "2") (name "+3V3_ADC") (class "Default")
      (node (ref "ADC1") (pin "15") (pinfunction "VREF_15") (pintype "bidirectional"))
      (node (ref "ADC1") (pin "16") (pinfunction "VDD_16") (pintype "bidirectional"))
      (node (ref "ADC2") (pin "15") (pinfunction "VREF_15") (pintype "bidirectional"))
      (node (ref "ADC2") (pin "16") (pinfunction "VDD_16") (pintype "bidirectional"))
      (node (ref "ADC3") (pin "15") (pinfunction "VREF_15") (pintype "bidirectional"))
      (node (ref "ADC3") (pin "16") (pinfunction "VDD_16") (pintype "bidirectional"))
      (node (ref "C1") (pin "1") (pinfunction "1_1") (pintype "passive"))
      (node (ref "C2") (pin "1") (pinfunction "1_1") (pintype "passive"))
      (node (ref "C3") (pin "1") (pinfunction "1_1") (pintype "passive"))
      (node (ref "JP1") (pin "2") (pinfunction "2_2") (pintype "passive"))
      (node (ref "R25") (pin "2") (pinfunction "2_2") (pintype "passive"))
      (node (ref "R29") (pin "2") (pinfunction "2_2") (pintype "passive"))
      (node (ref "R30") (pin "2") (pinfunction "2_2") (pintype "passive"))
    )
    (net (code "3") (name "+3V3_LC") (class "Default")
      (node (ref "C10") (pin "1") (pinfunction "1_1") (pintype "passive"))
      (node (ref "C11") (pin "1") (pinfunction "1_1") (pintype "passive"))
      (node (ref "C12") (pin "1") (pinfunction "1_1") (pintype "passive"))
      (node (ref "C13") (pin "1") (pinfunction "1_1") (pintype "passive"))
      (node (ref "JP3") (pin "2") (pinfunction "2_2") (pintype "passive"))
      (node (ref "R12") (pin "2") (pinfunction "2_2") (pintype "passive"))
      (node (ref "R17") (pin "2") (pinfunction "2_2") (pintype "passive"))
      (node (ref "R21") (pin "2") (pinfunction "2_2") (pintype "passive"))
      (node (ref "R9") (pin "2") (pinfunction "2_2") (pintype "passive"))
      (node (ref "U2") (pin "3") (pinfunction "VS+_3") (pintype "power_in"))
      (node (ref "U3") (pin "3") (pinfunction "VS+_3") (pintype "power_in"))
      (node (ref "U4") (pin "3") (pinfunction "VS+_3") (pintype "power_in"))
      (node (ref "U5") (pin "3") (pinfunction "VS+_3") (pintype "power_in"))
    )
    (net (code "4") (name "+3V3_PT") (class "Default")
      (node (ref "C14") (pin "1") (pinfunction "1_1") (pintype "passive"))
      (node (ref "C15") (pin "1") (pinfunction "1_1") (pintype "passive"))
      (node (ref "C18") (pin "1") (pinfunction "1_1") (pintype "passive"))
      (node (ref "C21") (pin "1") (pinfunction "1_1") (pintype "passive"))
      (node (ref "C24") (pin "1") (pinfunction "1_1") (pintype "passive"))
      (node (ref "C27") (pin "1") (pinfunction "1_1") (pintype "passive"))
      (node (ref "C8") (pin "1") (pinfunction "1_1") (pintype "passive"))
      (node (ref "C9") (pin "1") (pinfunction "1_1") (pintype "passive"))
      (node (ref "IC1") (pin "5") (pinfunction "+VS_5") (pintype "input"))
      (node (ref "IC2") (pin "5") (pinfunction "+VS_5") (pintype "input"))
      (node (ref "IC3") (pin "5") (pinfunction "+VS_5") (pintype "input"))
      (node (ref "IC4") (pin "5") (pinfunction "+VS_5") (pintype "input"))
      (node (ref "IC6") (pin "5") (pinfunction "+VS_5") (pintype "input"))
      (node (ref "IC7") (pin "5") (pinfunction "+VS_5") (pintype "input"))
      (node (ref "IC8") (pin "5") (pinfunction "+VS_5") (pintype "input"))
      (node (ref "IC9") (pin "5") (pinfunction "+VS_5") (pintype "input"))
      (node (ref "JP2") (pin "2") (pinfunction "2_2") (pintype "passive"))
      (node (ref "R38") (pin "1") (pinfunction "1_1") (pintype "passive"))
      (node (ref "R44") (pin "1") (pinfunction "1_1") (pintype "passive"))
      (node (ref "R53") (pin "1") (pinfunction "1_1") (pintype "passive"))
      (node (ref "R58") (pin "1") (pinfunction "1_1") (pintype "passive"))
    )
    (net (code "5") (name "+5V") (class "Default")
      (node (ref "C5") (pin "+") (pinfunction "+_+") (pintype "passive"))
      (node (ref "C7") (pin "+") (pinfunction "+_+") (pintype "passive"))
      (node (ref "LED2") (pin "A") (pinfunction "A_A") (pintype "passive"))
      (node (ref "REG1") (pin "3") (pinfunction "VIN_3") (pintype "passive"))
      (node (ref "U$5") (pin "A1") (pinfunction "1_A1") (pintype "bidirectional"))
      (node (ref "U$5") (pin "B1") (pinfunction "1_B1") (pintype "bidirectional"))
      (node (ref "U1") (pin "2") (pinfunction "VOUT_2") (pintype "input"))
      (node (ref "U1") (pin "4") (pinfunction "4_4") (pintype "passive"))
    )
    (net (code "6") (name "+5V_RPI") (class "Default")
      (node (ref "RPI_GPIO") (pin "2") (pinfunction "KL_2") (pintype "passive"))
    )
    (net (code "7") (name "+10V") (class "Default")
      (node (ref "C16") (pin "+") (pinfunction "+_+") (pintype "passive"))
      (node (ref "C6") (pin "+") (pinfunction "+_+") (pintype "passive"))
      (node (ref "IC5") (pin "3") (pinfunction "VO_3") (pintype "passive"))
      (node (ref "R35") (pin "2") (pinfunction "2_2") (pintype "passive"))
      (node (ref "U$4") (pin "A2") (pinfunction "2_A2") (pintype "bidirectional"))
      (node (ref "U$4") (pin "B2") (pinfunction "2_B2") (pintype "bidirectional"))
      (node (ref "U1") (pin "3") (pinfunction "VIN_3") (pintype "passive"))
    )
    (net (code "8") (name "+12V") (class "Default")
      (node (ref "C17") (pin "+") (pinfunction "+_+") (pintype "passive"))
      (node (ref "D1") (pin "C") (pinfunction "C_C") (pintype "passive"))
      (node (ref "D2") (pin "C") (pinfunction "C_C") (pintype "passive"))
      (node (ref "D3") (pin "C") (pinfunction "C_C") (pintype "passive"))
      (node (ref "D4") (pin "C") (pinfunction "C_C") (pintype "passive"))
      (node (ref "D5") (pin "C") (pinfunction "C_C") (pintype "passive"))
      (node (ref "IC5") (pin "1") (pinfunction "VI_1") (pintype "input"))
      (node (ref "LED1") (pin "A") (pinfunction "A_A") (pintype "passive"))
      (node (ref "PT_123_IN") (pin "P$10") (pinfunction "SK_P$10") (pintype "passive"))
      (node (ref "PT_123_IN") (pin "P$12") (pinfunction "SK_P$12") (pintype "passive"))
      (node (ref "PT_123_IN") (pin "P$2") (pinfunction "SK_P$2") (pintype "passive"))
      (node (ref "PT_123_IN") (pin "P$4") (pinfunction "SK_P$4") (pintype "passive"))
      (node (ref "PT_123_IN") (pin "P$6") (pinfunction "SK_P$6") (pintype "passive"))
      (node (ref "PT_123_IN") (pin "P$8") (pinfunction "SK_P$8") (pintype "passive"))
      (node (ref "TC_PT4_IN") (pin "P$12") (pinfunction "SK_P$12") (pintype "passive"))
      (node (ref "TC_PT4_IN") (pin "P$6") (pinfunction "SK_P$6") (pintype "passive"))
      (node (ref "U$4") (pin "A1") (pinfunction "1_A1") (pintype "bidirectional"))
      (node (ref "U$4") (pin "B1") (pinfunction "1_B1") (pintype "bidirectional"))
    )
    (net (code "9") (name "+12V_DEBUG") (class "Default")
      (node (ref "U$1") (pin "A1") (pinfunction "1_A1") (pintype "bidirectional"))
      (node (ref "U$1") (pin "B1") (pinfunction "1_B1") (pintype "bidirectional"))
      (node (ref "U6") (pin "2") (pinfunction "P_2") (pintype "passive"))
    )
    (net (code "16") (name "ADC1_A0") (class "Default")
      (node (ref "ADC1") (pin "1") (pinfunction "CH0_1") (pintype "bidirectional"))
      (node (ref "R11") (pin "2") (pinfunction "2_2") (pintype "passive"))
      (node (ref "U2") (pin "5") (pinfunction "VOUT-_5") (pintype "output"))
      (node (ref "X4") (pin "1") (pinfunction "1_1") (pintype "passive"))
    )
    (net (code "17") (name "ADC1_A1") (class "Default")
      (node (ref "ADC1") (pin "2") (pinfunction "CH1_2") (pintype "bidirectional"))
      (node (ref "R14") (pin "2") (pinfunction "2_2") (pintype "passive"))
      (node (ref "U2") (pin "4") (pinfunction "VOUT+_4") (pintype "output"))
      (node (ref "X4") (pin "2") (pinfunction "1_2") (pintype "passive"))
    )
    (net (code "18") (name "ADC1_A2") (class "Default")
      (node (ref "ADC1") (pin "3") (pinfunction "CH2_3") (pintype "bidirectional"))
      (node (ref "R15") (pin "2") (pinfunction "2_2") (pintype "passive"))
      (node (ref "U3") (pin "5") (pinfunction "VOUT-_5") (pintype "output"))
      (node (ref "X4") (pin "3") (pinfunction "1_3") (pintype "passive"))
    )
    (net (code "19") (name "ADC1_A3") (class "Default")
      (node (ref "ADC1") (pin "4") (pinfunction "CH3_4") (pintype "bidirectional"))
      (node (ref "R16") (pin "2") (pinfunction "2_2") (pintype "passive"))
      (node (ref "U3") (pin "4") (pinfunction "VOUT+_4") (pintype "output"))
      (node (ref "X4") (pin "4") (pinfunction "1_4") (pintype "passive"))
    )
    (net (code "20") (name "ADC1_A4") (class "Default")
      (node (ref "ADC1") (pin "5") (pinfunction "CH4_5") (pintype "bidirectional"))
      (node (ref "R19") (pin "2") (pinfunction "2_2") (pintype "passive"))
      (node (ref "U4") (pin "5") (pinfunction "VOUT-_5") (pintype "output"))
      (node (ref "X4") (pin "5") (pinfunction "1_5") (pintype "passive"))
    )
    (net (code "21") (name "ADC1_A5") (class "Default")
      (node (ref "ADC1") (pin "6") (pinfunction "CH5_6") (pintype "bidirectional"))
      (node (ref "R20") (pin "2") (pinfunction "2_2") (pintype "passive"))
      (node (ref "U4") (pin "4") (pinfunction "VOUT+_4") (pintype "output"))
      (node (ref "X4") (pin "6") (pinfunction "1_6") (pintype "passive"))
    )
    (net (code "22") (name "ADC1_A6") (class "Default")
      (node (ref "ADC1") (pin "7") (pinfunction "CH6_7") (pintype "bidirectional"))
      (node (ref "R23") (pin "2") (pinfunction "2_2") (pintype "passive"))
      (node (ref "U5") (pin "5") (pinfunction "VOUT-_5") (pintype "output"))
      (node (ref "X4") (pin "7") (pinfunction "1_7") (pintype "passive"))
    )
    (net (code "23") (name "ADC1_A7") (class "Default")
      (node (ref "ADC1") (pin "8") (pinfunction "CH7_8") (pintype "bidirectional"))
      (node (ref "R24") (pin "2") (pinfunction "2_2") (pintype "passive"))
      (node (ref "U5") (pin "4") (pinfunction "VOUT+_4") (pintype "output"))
      (node (ref "X4") (pin "8") (pinfunction "1_8") (pintype "passive"))
    )
    (net (code "24") (name "ADC1_CS") (class "Default")
      (node (ref "ADC1") (pin "10") (pinfunction "CS*_10") (pintype "bidirectional"))
      (node (ref "R25") (pin "1") (pinfunction "1_1") (pintype "passive"))
      (node (ref "RPI_GPIO") (pin "22") (pinfunction "KL_22") (pintype "passive"))
    )
    (net (code "25") (name "ADC2_A0") (class "Default")
      (node (ref "ADC2") (pin "1") (pinfunction "CH0_1") (pintype "bidirectional"))
      (node (ref "IC6") (pin "3") (pinfunction "IN-_3") (pintype "input"))
      (node (ref "IC6") (pin "4") (pinfunction "OUT_4") (pintype "output"))
      (node (ref "X7") (pin "1") (pinfunction "1_1") (pintype "passive"))
    )
    (net (code "26") (name "ADC2_A1") (class "Default")
      (node (ref "ADC2") (pin "2") (pinfunction "CH1_2") (pintype "bidirectional"))
      (node (ref "IC7") (pin "3") (pinfunction "IN-_3") (pintype "input"))
      (node (ref "IC7") (pin "4") (pinfunction "OUT_4") (pintype "output"))
      (node (ref "X7") (pin "2") (pinfunction "1_2") (pintype "passive"))
    )
    (net (code "27") (name "ADC2_A2") (class "Default")
      (node (ref "ADC2") (pin "3") (pinfunction "CH2_3") (pintype "bidirectional"))
      (node (ref "IC8") (pin "3") (pinfunction "IN-_3") (pintype "input"))
      (node (ref "IC8") (pin "4") (pinfunction "OUT_4") (pintype "output"))
      (node (ref "X7") (pin "3") (pinfunction "1_3") (pintype "passive"))
    )
    (net (code "28") (name "ADC2_A3") (class "Default")
      (node (ref "ADC2") (pin "4") (pinfunction "CH3_4") (pintype "bidirectional"))
      (node (ref "IC9") (pin "3") (pinfunction "IN-_3") (pintype "input"))
      (node (ref "IC9") (pin "4") (pinfunction "OUT_4") (pintype "output"))
      (node (ref "X7") (pin "4") (pinfunction "1_4") (pintype "passive"))
    )
    (net (code "29") (name "ADC2_A4") (class "Default")
      (node (ref "ADC2") (pin "5") (pinfunction "CH4_5") (pintype "bidirectional"))
      (node (ref "TC_PT4_IN") (pin "P$10") (pinfunction "SK_P$10") (pintype "passive"))
      (node (ref "TC_PT4_IN") (pin "P$4") (pinfunction "SK_P$4") (pintype "passive"))
      (node (ref "X7") (pin "5") (pinfunction "1_5") (pintype "passive"))
    )
    (net (code "30") (name "ADC2_A5") (class "Default")
      (node (ref "ADC2") (pin "6") (pinfunction "CH5_6") (pintype "bidirectional"))
      (node (ref "TC_PT4_IN") (pin "P$3") (pinfunction "SK_P$3") (pintype "passive"))
      (node (ref "TC_PT4_IN") (pin "P$9") (pinfunction "SK_P$9") (pintype "passive"))
      (node (ref "X7") (pin "6") (pinfunction "1_6") (pintype "passive"))
    )
    (net (code "31") (name "ADC2_A6") (class "Default")
      (node (ref "ADC2") (pin "7") (pinfunction "CH6_7") (pintype "bidirectional"))
      (node (ref "TC_PT4_IN") (pin "P$2") (pinfunction "SK_P$2") (pintype "passive"))
      (node (ref "TC_PT4_IN") (pin "P$8") (pinfunction "SK_P$8") (pintype "passive"))
      (node (ref "X7") (pin "7") (pinfunction "1_7") (pintype "passive"))
    )
    (net (code "32") (name "ADC2_A7") (class "Default")
      (node (ref "ADC2") (pin "8") (pinfunction "CH7_8") (pintype "bidirectional"))
      (node (ref "TC_PT4_IN") (pin "P$1") (pinfunction "SK_P$1") (pintype "passive"))
      (node (ref "TC_PT4_IN") (pin "P$7") (pinfunction "SK_P$7") (pintype "passive"))
      (node (ref "X7") (pin "8") (pinfunction "1_8") (pintype "passive"))
    )
    (net (code "33") (name "ADC2_CS") (class "Default")
      (node (ref "ADC2") (pin "10") (pinfunction "CS*_10") (pintype "bidirectional"))
      (node (ref "R29") (pin "1") (pinfunction "1_1") (pintype "passive"))
      (node (ref "RPI_GPIO") (pin "24") (pinfunction "KL_24") (pintype "passive"))
    )
    (net (code "34") (name "ADC3_A0") (class "Default")
      (node (ref "ADC3") (pin "1") (pinfunction "CH0_1") (pintype "bidirectional"))
      (node (ref "X8") (pin "1") (pinfunction "1_1") (pintype "passive"))
    )
    (net (code "35") (name "ADC3_A1") (class "Default")
      (node (ref "ADC3") (pin "2") (pinfunction "CH1_2") (pintype "bidirectional"))
      (node (ref "X8") (pin "2") (pinfunction "1_2") (pintype "passive"))
    )
    (net (code "36") (name "ADC3_A2") (class "Default")
      (node (ref "ADC3") (pin "3") (pinfunction "CH2_3") (pintype "bidirectional"))
      (node (ref "X8") (pin "3") (pinfunction "1_3") (pintype "passive"))
    )
    (net (code "37") (name "ADC3_A3") (class "Default")
      (node (ref "ADC3") (pin "4") (pinfunction "CH3_4") (pintype "bidirectional"))
      (node (ref "X8") (pin "4") (pinfunction "1_4") (pintype "passive"))
    )
    (net (code "38") (name "ADC3_A4") (class "Default")
      (node (ref "ADC3") (pin "5") (pinfunction "CH4_5") (pintype "bidirectional"))
      (node (ref "X8") (pin "5") (pinfunction "1_5") (pintype "passive"))
    )
    (net (code "39") (name "ADC3_A5") (class "Default")
      (node (ref "ADC3") (pin "6") (pinfunction "CH5_6") (pintype "bidirectional"))
      (node (ref "X8") (pin "6") (pinfunction "1_6") (pintype "passive"))
    )
    (net (code "40") (name "ADC3_A6") (class "Default")
      (node (ref "ADC3") (pin "7") (pinfunction "CH6_7") (pintype "bidirectional"))
      (node (ref "X8") (pin "7") (pinfunction "1_7") (pintype "passive"))
    )
    (net (code "41") (name "ADC3_A7") (class "Default")
      (node (ref "ADC3") (pin "8") (pinfunction "CH7_8") (pintype "bidirectional"))
      (node (ref "X8") (pin "8") (pinfunction "1_8") (pintype "passive"))
    )
    (net (code "42") (name "ADC3_CS") (class "Default")
      (node (ref "ADC3") (pin "10") (pinfunction "CS*_10") (pintype "bidirectional"))
      (node (ref "R30") (pin "1") (pinfunction "1_1") (pintype "passive"))
      (node (ref "RPI_GPIO") (pin "26") (pinfunction "KL_26") (pintype "passive"))
    )
    (net (code "43") (name "CTRL_SOLENOID_1") (class "Default")
      (node (ref "R3") (pin "1") (pinfunction "1_1") (pintype "passive"))
      (node (ref "RPI_GPIO") (pin "11") (pinfunction "KL_11") (pintype "passive"))
    )
    (net (code "44") (name "CTRL_SOLENOID_2") (class "Default")
      (node (ref "R5") (pin "1") (pinfunction "1_1") (pintype "passive"))
      (node (ref "RPI_GPIO") (pin "13") (pinfunction "KL_13") (pintype "passive"))
    )
    (net (code "45") (name "CTRL_SOLENOID_3") (class "Default")
      (node (ref "R7") (pin "1") (pinfunction "1_1") (pintype "passive"))
      (node (ref "RPI_GPIO") (pin "15") (pinfunction "KL_15") (pintype "passive"))
    )
    (net (code "46") (name "GND") (class "Default")
      (node (ref "ADC1") (pin "14") (pinfunction "AGND_14") (pintype "bidirectional"))
      (node (ref "ADC1") (pin "9") (pinfunction "DGND_9") (pintype "bidirectional"))
      (node (ref "ADC2") (pin "14") (pinfunction "AGND_14") (pintype "bidirectional"))
      (node (ref "ADC2") (pin "9") (pinfunction "DGND_9") (pintype "bidirectional"))
      (node (ref "ADC3") (pin "14") (pinfunction "AGND_14") (pintype "bidirectional"))
      (node (ref "ADC3") (pin "9") (pinfunction "DGND_9") (pintype "bidirectional"))
      (node (ref "C1") (pin "2") (pinfunction "2_2") (pintype "passive"))
      (node (ref "C10") (pin "2") (pinfunction "2_2") (pintype "passive"))
      (node (ref "C11") (pin "2") (pinfunction "2_2") (pintype "passive"))
      (node (ref "C12") (pin "2") (pinfunction "2_2") (pintype "passive"))
      (node (ref "C13") (pin "2") (pinfunction "2_2") (pintype "passive"))
      (node (ref "C14") (pin "2") (pinfunction "2_2") (pintype "passive"))
      (node (ref "C15") (pin "2") (pinfunction "2_2") (pintype "passive"))
      (node (ref "C16") (pin "-") (pinfunction "-_-") (pintype "passive"))
      (node (ref "C17") (pin "-") (pinfunction "-_-") (pintype "passive"))
      (node (ref "C18") (pin "2") (pinfunction "2_2") (pintype "passive"))
      (node (ref "C19") (pin "2") (pinfunction "2_2") (pintype "passive"))
      (node (ref "C2") (pin "2") (pinfunction "2_2") (pintype "passive"))
      (node (ref "C20") (pin "2") (pinfunction "2_2") (pintype "passive"))
      (node (ref "C21") (pin "2") (pinfunction "2_2") (pintype "passive"))
      (node (ref "C22") (pin "2") (pinfunction "2_2") (pintype "passive"))
      (node (ref "C23") (pin "2") (pinfunction "2_2") (pintype "passive"))
      (node (ref "C24") (pin "2") (pinfunction "2_2") (pintype "passive"))
      (node (ref "C25") (pin "2") (pinfunction "2_2") (pintype "passive"))
      (node (ref "C26") (pin "2") (pinfunction "2_2") (pintype "passive"))
      (node (ref "C27") (pin "2") (pinfunction "2_2") (pintype "passive"))
      (node (ref "C28") (pin "2") (pinfunction "2_2") (pintype "passive"))
      (node (ref "C29") (pin "2") (pinfunction "2_2") (pintype "passive"))
      (node (ref "C3") (pin "2") (pinfunction "2_2") (pintype "passive"))
      (node (ref "C4") (pin "-") (pinfunction "-_-") (pintype "passive"))
      (node (ref "C5") (pin "-") (pinfunction "-_-") (pintype "passive"))
      (node (ref "C6") (pin "-") (pinfunction "-_-") (pintype "passive"))
      (node (ref "C7") (pin "-") (pinfunction "-_-") (pintype "passive"))
      (node (ref "C8") (pin "2") (pinfunction "2_2") (pintype "passive"))
      (node (ref "C9") (pin "2") (pinfunction "2_2") (pintype "passive"))
      (node (ref "IC1") (pin "2") (pinfunction "-VS_2") (pintype "input"))
      (node (ref "IC2") (pin "2") (pinfunction "-VS_2") (pintype "input"))
      (node (ref "IC3") (pin "2") (pinfunction "-VS_2") (pintype "input"))
      (node (ref "IC4") (pin "2") (pinfunction "-VS_2") (pintype "input"))
      (node (ref "IC5") (pin "2") (pinfunction "GND_2") (pintype "passive"))
      (node (ref "IC6") (pin "2") (pinfunction "-VS_2") (pintype "input"))
      (node (ref "IC7") (pin "2") (pinfunction "-VS_2") (pintype "input"))
      (node (ref "IC8") (pin "2") (pinfunction "-VS_2") (pintype "input"))
      (node (ref "IC9") (pin "2") (pinfunction "-VS_2") (pintype "input"))
      (node (ref "LED4") (pin "A") (pinfunction "A_A") (pintype "passive"))
      (node (ref "R2") (pin "2") (pinfunction "2_2") (pintype "passive"))
      (node (ref "R26") (pin "1") (pinfunction "1_1") (pintype "passive"))
      (node (ref "R27") (pin "2") (pinfunction "2_2") (pintype "passive"))
      (node (ref "R28") (pin "2") (pinfunction "2_2") (pintype "passive"))
      (node (ref "R31") (pin "1") (pinfunction "1_1") (pintype "passive"))
      (node (ref "R32") (pin "1") (pinfunction "1_1") (pintype "passive"))
      (node (ref "R33") (pin "1") (pinfunction "1_1") (pintype "passive"))
      (node (ref "R39") (pin "2") (pinfunction "2_2") (pintype "passive"))
      (node (ref "R4") (pin "2") (pinfunction "2_2") (pintype "passive"))
      (node (ref "R45") (pin "2") (pinfunction "2_2") (pintype "passive"))
      (node (ref "R54") (pin "2") (pinfunction "2_2") (pintype "passive"))
      (node (ref "R55") (pin "1") (pinfunction "1_1") (pintype "passive"))
      (node (ref "R59") (pin "2") (pinfunction "2_2") (pintype "passive"))
      (node (ref "R6") (pin "2") (pinfunction "2_2") (pintype "passive"))
      (node (ref "R8") (pin "2") (pinfunction "2_2") (pintype "passive"))
      (node (ref "REG1") (pin "1") (pinfunction "GND_1") (pintype "passive"))
      (node (ref "RPI_GPIO") (pin "6") (pinfunction "KL_6") (pintype "passive"))
      (node (ref "U$1") (pin "A2") (pinfunction "2_A2") (pintype "bidirectional"))
      (node (ref "U$1") (pin "B2") (pinfunction "2_B2") (pintype "bidirectional"))
      (node (ref "U$2") (pin "2") (pinfunction "S_2") (pintype "passive"))
      (node (ref "U$3") (pin "2") (pinfunction "S_2") (pintype "passive"))
      (node (ref "U$5") (pin "A2") (pinfunction "2_A2") (pintype "bidirectional"))
      (node (ref "U$5") (pin "B2") (pinfunction "2_B2") (pintype "bidirectional"))
      (node (ref "U$8") (pin "2") (pinfunction "S_2") (pintype "passive"))
      (node (ref "U$9") (pin "2") (pinfunction "S_2") (pintype "passive"))
      (node (ref "U1") (pin "1") (pinfunction "GND_1") (pintype "output"))
      (node (ref "U2") (pin "6") (pinfunction "VS-_6") (pintype "power_in"))
      (node (ref "U3") (pin "6") (pinfunction "VS-_6") (pintype "power_in"))
      (node (ref "U4") (pin "6") (pinfunction "VS-_6") (pintype "power_in"))
      (node (ref "U5") (pin "6") (pinfunction "VS-_6") (pintype "power_in"))
    )
    (net (code "47") (name "IGNITION_RELAY") (class "Default")
      (node (ref "R1") (pin "1") (pinfunction "1_1") (pintype "passive"))
      (node (ref "RPI_GPIO") (pin "16") (pinfunction "KL_16") (pintype "passive"))
    )
    (net (code "48") (name "LC_1_OUT+") (class "Default")
      (node (ref "LC_IN1") (pin "P$3") (pinfunction "SK_P$3") (pintype "passive"))
      (node (ref "LC_IN1") (pin "P$7") (pinfunction "SK_P$7") (pintype "passive"))
      (node (ref "R10") (pin "2-2") (pinfunction "S_2-2") (pintype "passive"))
    )
    (net (code "49") (name "LC_1_OUT-") (class "Default")
      (node (ref "LC_IN1") (pin "P$4") (pinfunction "SK_P$4") (pintype "passive"))
      (node (ref "LC_IN1") (pin "P$8") (pinfunction "SK_P$8") (pintype "passive"))
      (node (ref "R10") (pin "1-2") (pinfunction "S_1-2") (pintype "passive"))
    )
    (net (code "50") (name "LC_2_OUT+") (class "Default")
      (node (ref "LC_IN1") (pin "P$1") (pinfunction "SK_P$1") (pintype "passive"))
      (node (ref "LC_IN1") (pin "P$5") (pinfunction "SK_P$5") (pintype "passive"))
      (node (ref "R13") (pin "2-2") (pinfunction "S_2-2") (pintype "passive"))
    )
    (net (code "51") (name "LC_2_OUT-") (class "Default")
      (node (ref "LC_IN1") (pin "P$2") (pinfunction "SK_P$2") (pintype "passive"))
      (node (ref "LC_IN1") (pin "P$6") (pinfunction "SK_P$6") (pintype "passive"))
      (node (ref "R13") (pin "1-2") (pinfunction "S_1-2") (pintype "passive"))
    )
    (net (code "52") (name "LC_3_OUT+") (class "Default")
      (node (ref "LC_IN2") (pin "P$3") (pinfunction "SK_P$3") (pintype "passive"))
      (node (ref "LC_IN2") (pin "P$7") (pinfunction "SK_P$7") (pintype "passive"))
      (node (ref "R18") (pin "2-2") (pinfunction "S_2-2") (pintype "passive"))
    )
    (net (code "53") (name "LC_3_OUT-") (class "Default")
      (node (ref "LC_IN2") (pin "P$4") (pinfunction "SK_P$4") (pintype "passive"))
      (node (ref "LC_IN2") (pin "P$8") (pinfunction "SK_P$8") (pintype "passive"))
      (node (ref "R18") (pin "1-2") (pinfunction "S_1-2") (pintype "passive"))
    )
    (net (code "54") (name "LC_4_OUT+") (class "Default")
      (node (ref "LC_IN2") (pin "P$1") (pinfunction "SK_P$1") (pintype "passive"))
      (node (ref "LC_IN2") (pin "P$5") (pinfunction "SK_P$5") (pintype "passive"))
      (node (ref "R22") (pin "2-2") (pinfunction "S_2-2") (pintype "passive"))
    )
    (net (code "55") (name "LC_4_OUT-") (class "Default")
      (node (ref "LC_IN2") (pin "P$2") (pinfunction "SK_P$2") (pintype "passive"))
      (node (ref "LC_IN2") (pin "P$6") (pinfunction "SK_P$6") (pintype "passive"))
      (node (ref "R22") (pin "1-2") (pinfunction "S_1-2") (pintype "passive"))
    )
    (net (code "56") (name "MISO") (class "Default")
      (node (ref "ADC1") (pin "12") (pinfunction "DOUT_12") (pintype "bidirectional"))
      (node (ref "ADC2") (pin "12") (pinfunction "DOUT_12") (pintype "bidirectional"))
      (node (ref "ADC3") (pin "12") (pinfunction "DOUT_12") (pintype "bidirectional"))
      (node (ref "RPI_GPIO") (pin "21") (pinfunction "KL_21") (pintype "passive"))
    )
    (net (code "57") (name "MOSI") (class "Default")
      (node (ref "ADC1") (pin "11") (pinfunction "DIN_11") (pintype "bidirectional"))
      (node (ref "ADC2") (pin "11") (pinfunction "DIN_11") (pintype "bidirectional"))
      (node (ref "ADC3") (pin "11") (pinfunction "DIN_11") (pintype "bidirectional"))
      (node (ref "RPI_GPIO") (pin "19") (pinfunction "KL_19") (pintype "passive"))
    )
    (net (code "58") (name "Net-(C19-Pad1)") (class "Default")
      (node (ref "C19") (pin "1") (pinfunction "1_1") (pintype "passive"))
      (node (ref "R40") (pin "2") (pinfunction "2_2") (pintype "passive"))
      (node (ref "R41") (pin "1") (pinfunction "1_1") (pintype "passive"))
    )
    (net (code "59") (name "Net-(C22-Pad1)") (class "Default")
      (node (ref "C22") (pin "1") (pinfunction "1_1") (pintype "passive"))
      (node (ref "R46") (pin "1") (pinfunction "1_1") (pintype "passive"))
      (node (ref "R47") (pin "2") (pinfunction "2_2") (pintype "passive"))
    )
    (net (code "60") (name "Net-(C25-Pad1)") (class "Default")
      (node (ref "C25") (pin "1") (pinfunction "1_1") (pintype "passive"))
      (node (ref "R48") (pin "1") (pinfunction "1_1") (pintype "passive"))
      (node (ref "R49") (pin "2") (pinfunction "2_2") (pintype "passive"))
    )
    (net (code "61") (name "Net-(C28-Pad1)") (class "Default")
      (node (ref "C28") (pin "1") (pinfunction "1_1") (pintype "passive"))
      (node (ref "R50") (pin "1") (pinfunction "1_1") (pintype "passive"))
      (node (ref "R51") (pin "2") (pinfunction "2_2") (pintype "passive"))
    )
    (net (code "62") (name "Net-(IC1-IN+)") (class "Default")
      (node (ref "IC1") (pin "1") (pinfunction "IN+_1") (pintype "input"))
      (node (ref "R38") (pin "2") (pinfunction "2_2") (pintype "passive"))
      (node (ref "R39") (pin "1") (pinfunction "1_1") (pintype "passive"))
    )
    (net (code "63") (name "Net-(IC1-IN-)") (class "Default")
      (node (ref "IC1") (pin "3") (pinfunction "IN-_3") (pintype "input"))
      (node (ref "R36") (pin "1") (pinfunction "1_1") (pintype "passive"))
      (node (ref "R37") (pin "2") (pinfunction "2_2") (pintype "passive"))
    )
    (net (code "64") (name "Net-(IC2-IN+)") (class "Default")
      (node (ref "IC2") (pin "1") (pinfunction "IN+_1") (pintype "input"))
      (node (ref "R44") (pin "2") (pinfunction "2_2") (pintype "passive"))
      (node (ref "R45") (pin "1") (pinfunction "1_1") (pintype "passive"))
    )
    (net (code "65") (name "Net-(IC2-IN-)") (class "Default")
      (node (ref "IC2") (pin "3") (pinfunction "IN-_3") (pintype "input"))
      (node (ref "R42") (pin "1") (pinfunction "1_1") (pintype "passive"))
      (node (ref "R43") (pin "2") (pinfunction "2_2") (pintype "passive"))
    )
    (net (code "66") (name "Net-(IC3-IN+)") (class "Default")
      (node (ref "IC3") (pin "1") (pinfunction "IN+_1") (pintype "input"))
      (node (ref "R53") (pin "2") (pinfunction "2_2") (pintype "passive"))
      (node (ref "R54") (pin "1") (pinfunction "1_1") (pintype "passive"))
    )
    (net (code "67") (name "Net-(IC3-IN-)") (class "Default")
      (node (ref "IC3") (pin "3") (pinfunction "IN-_3") (pintype "input"))
      (node (ref "R34") (pin "1") (pinfunction "1_1") (pintype "passive"))
      (node (ref "R52") (pin "2") (pinfunction "2_2") (pintype "passive"))
    )
    (net (code "68") (name "Net-(IC4-IN+)") (class "Default")
      (node (ref "IC4") (pin "1") (pinfunction "IN+_1") (pintype "input"))
      (node (ref "R58") (pin "2") (pinfunction "2_2") (pintype "passive"))
      (node (ref "R59") (pin "1") (pinfunction "1_1") (pintype "passive"))
    )
    (net (code "69") (name "Net-(IC4-IN-)") (class "Default")
      (node (ref "IC4") (pin "3") (pinfunction "IN-_3") (pintype "input"))
      (node (ref "R56") (pin "1") (pinfunction "1_1") (pintype "passive"))
      (node (ref "R57") (pin "2") (pinfunction "2_2") (pintype "passive"))
    )
    (net (code "70") (name "Net-(IC6-IN+)") (class "Default")
      (node (ref "C20") (pin "1") (pinfunction "1_1") (pintype "passive"))
      (node (ref "IC6") (pin "1") (pinfunction "IN+_1") (pintype "input"))
      (node (ref "R40") (pin "1") (pinfunction "1_1") (pintype "passive"))
    )
    (net (code "71") (name "Net-(IC7-IN+)") (class "Default")
      (node (ref "C23") (pin "1") (pinfunction "1_1") (pintype "passive"))
      (node (ref "IC7") (pin "1") (pinfunction "IN+_1") (pintype "input"))
      (node (ref "R47") (pin "1") (pinfunction "1_1") (pintype "passive"))
    )
    (net (code "72") (name "Net-(IC8-IN+)") (class "Default")
      (node (ref "C26") (pin "1") (pinfunction "1_1") (pintype "passive"))
      (node (ref "IC8") (pin "1") (pinfunction "IN+_1") (pintype "input"))
      (node (ref "R49") (pin "1") (pinfunction "1_1") (pintype "passive"))
    )
    (net (code "73") (name "Net-(IC9-IN+)") (class "Default")
      (node (ref "C29") (pin "1") (pinfunction "1_1") (pintype "passive"))
      (node (ref "IC9") (pin "1") (pinfunction "IN+_1") (pintype "input"))
      (node (ref "R51") (pin "1") (pinfunction "1_1") (pintype "passive"))
    )
    (net (code "74") (name "Net-(LED1-C)") (class "Default")
      (node (ref "LED1") (pin "K") (pinfunction "C_K") (pintype "passive"))
      (node (ref "R26") (pin "2") (pinfunction "2_2") (pintype "passive"))
    )
    (net (code "75") (name "Net-(LED2-C)") (class "Default")
      (node (ref "LED2") (pin "K") (pinfunction "C_K") (pintype "passive"))
      (node (ref "R27") (pin "1") (pinfunction "1_1") (pintype "passive"))
    )
    (net (code "76") (name "Net-(LED3-C)") (class "Default")
      (node (ref "LED3") (pin "K") (pinfunction "C_K") (pintype "passive"))
      (node (ref "R28") (pin "1") (pinfunction "1_1") (pintype "passive"))
    )
    (net (code "77") (name "Net-(LED4-C)") (class "Default")
      (node (ref "LED4") (pin "K") (pinfunction "C_K") (pintype "passive"))
      (node (ref "R35") (pin "1") (pinfunction "1_1") (pintype "passive"))
    )
    (net (code "78") (name "Net-(R10A-A)") (class "Default")
      (node (ref "R10") (pin "1-1") (pinfunction "A_1-1") (pintype "passive"))
      (node (ref "R14") (pin "1") (pinfunction "1_1") (pintype "passive"))
      (node (ref "U2") (pin "1") (pinfunction "VIN-_1") (pintype "input"))
    )
    (net (code "79") (name "Net-(R10B-A)") (class "Default")
      (node (ref "R10") (pin "2-1") (pinfunction "A_2-1") (pintype "passive"))
      (node (ref "R11") (pin "1") (pinfunction "1_1") (pintype "passive"))
      (node (ref "U2") (pin "8") (pinfunction "VIN+_8") (pintype "input"))
    )
    (net (code "80") (name "Net-(R13A-A)") (class "Default")
      (node (ref "R13") (pin "1-1") (pinfunction "A_1-1") (pintype "passive"))
      (node (ref "R16") (pin "1") (pinfunction "1_1") (pintype "passive"))
      (node (ref "U3") (pin "1") (pinfunction "VIN-_1") (pintype "input"))
    )
    (net (code "81") (name "Net-(R13B-A)") (class "Default")
      (node (ref "R13") (pin "2-1") (pinfunction "A_2-1") (pintype "passive"))
      (node (ref "R15") (pin "1") (pinfunction "1_1") (pintype "passive"))
      (node (ref "U3") (pin "8") (pinfunction "VIN+_8") (pintype "input"))
    )
    (net (code "82") (name "Net-(R18A-A)") (class "Default")
      (node (ref "R18") (pin "1-1") (pinfunction "A_1-1") (pintype "passive"))
      (node (ref "R20") (pin "1") (pinfunction "1_1") (pintype "passive"))
      (node (ref "U4") (pin "1") (pinfunction "VIN-_1") (pintype "input"))
    )
    (net (code "83") (name "Net-(R18B-A)") (class "Default")
      (node (ref "R18") (pin "2-1") (pinfunction "A_2-1") (pintype "passive"))
      (node (ref "R19") (pin "1") (pinfunction "1_1") (pintype "passive"))
      (node (ref "U4") (pin "8") (pinfunction "VIN+_8") (pintype "input"))
    )
    (net (code "84") (name "Net-(R22A-A)") (class "Default")
      (node (ref "R22") (pin "1-1") (pinfunction "A_1-1") (pintype "passive"))
      (node (ref "R24") (pin "1") (pinfunction "1_1") (pintype "passive"))
      (node (ref "U5") (pin "1") (pinfunction "VIN-_1") (pintype "input"))
    )
    (net (code "85") (name "Net-(R22B-A)") (class "Default")
      (node (ref "R22") (pin "2-1") (pinfunction "A_2-1") (pintype "passive"))
      (node (ref "R23") (pin "1") (pinfunction "1_1") (pintype "passive"))
      (node (ref "U5") (pin "8") (pinfunction "VIN+_8") (pintype "input"))
    )
    (net (code "86") (name "Net-(U$2-G)") (class "Default")
      (node (ref "R1") (pin "2") (pinfunction "2_2") (pintype "passive"))
      (node (ref "R2") (pin "1") (pinfunction "1_1") (pintype "passive"))
      (node (ref "U$2") (pin "1") (pinfunction "G_1") (pintype "passive"))
    )
    (net (code "87") (name "Net-(U$3-G)") (class "Default")
      (node (ref "R3") (pin "2") (pinfunction "2_2") (pintype "passive"))
      (node (ref "R4") (pin "1") (pinfunction "1_1") (pintype "passive"))
      (node (ref "U$3") (pin "1") (pinfunction "G_1") (pintype "passive"))
    )
    (net (code "88") (name "Net-(U$8-G)") (class "Default")
      (node (ref "R5") (pin "2") (pinfunction "2_2") (pintype "passive"))
      (node (ref "R6") (pin "1") (pinfunction "1_1") (pintype "passive"))
      (node (ref "U$8") (pin "1") (pinfunction "G_1") (pintype "passive"))
    )
    (net (code "89") (name "Net-(U$9-G)") (class "Default")
      (node (ref "R7") (pin "2") (pinfunction "2_2") (pintype "passive"))
      (node (ref "R8") (pin "1") (pinfunction "1_1") (pintype "passive"))
      (node (ref "U$9") (pin "1") (pinfunction "G_1") (pintype "passive"))
    )
    (net (code "90") (name "Net-(U2-~{PD})") (class "Default")
      (node (ref "R9") (pin "1") (pinfunction "1_1") (pintype "passive"))
      (node (ref "U2") (pin "7") (pinfunction "~{PD}_7") (pintype "power_in"))
    )
    (net (code "91") (name "Net-(U3-~{PD})") (class "Default")
      (node (ref "R12") (pin "1") (pinfunction "1_1") (pintype "passive"))
      (node (ref "U3") (pin "7") (pinfunction "~{PD}_7") (pintype "power_in"))
    )
    (net (code "92") (name "Net-(U4-~{PD})") (class "Default")
      (node (ref "R17") (pin "1") (pinfunction "1_1") (pintype "passive"))
      (node (ref "U4") (pin "7") (pinfunction "~{PD}_7") (pintype "power_in"))
    )
    (net (code "93") (name "Net-(U5-~{PD})") (class "Default")
      (node (ref "R21") (pin "1") (pinfunction "1_1") (pintype "passive"))
      (node (ref "U5") (pin "7") (pinfunction "~{PD}_7") (pintype "power_in"))
    )
    (net (code "94") (name "Net-(U6-O)") (class "Default")
      (node (ref "D5") (pin "A") (pinfunction "A_A") (pintype "passive"))
      (node (ref "U6") (pin "1") (pinfunction "O_1") (pintype "passive"))
    )
    (net (code "95") (name "PT1_PREC") (class "Default")
      (node (ref "IC1") (pin "4") (pinfunction "OUT_4") (pintype "output"))
      (node (ref "R37") (pin "1") (pinfunction "1_1") (pintype "passive"))
      (node (ref "R41") (pin "2") (pinfunction "2_2") (pintype "passive"))
    )
    (net (code "96") (name "PT1_VS-") (class "Default")
      (node (ref "PT_123_IN") (pin "P$11") (pinfunction "SK_P$11") (pintype "passive"))
      (node (ref "PT_123_IN") (pin "P$5") (pinfunction "SK_P$5") (pintype "passive"))
      (node (ref "R31") (pin "2") (pinfunction "2_2") (pintype "passive"))
      (node (ref "R36") (pin "2") (pinfunction "2_2") (pintype "passive"))
    )
    (net (code "97") (name "PT2_PREC") (class "Default")
      (node (ref "IC2") (pin "4") (pinfunction "OUT_4") (pintype "output"))
      (node (ref "R43") (pin "1") (pinfunction "1_1") (pintype "passive"))
      (node (ref "R46") (pin "2") (pinfunction "2_2") (pintype "passive"))
    )
    (net (code "98") (name "PT2_VS-") (class "Default")
      (node (ref "PT_123_IN") (pin "P$3") (pinfunction "SK_P$3") (pintype "passive"))
      (node (ref "PT_123_IN") (pin "P$9") (pinfunction "SK_P$9") (pintype "passive"))
      (node (ref "R32") (pin "2") (pinfunction "2_2") (pintype "passive"))
      (node (ref "R42") (pin "2") (pinfunction "2_2") (pintype "passive"))
    )
    (net (code "99") (name "PT3_PREC") (class "Default")
      (node (ref "IC3") (pin "4") (pinfunction "OUT_4") (pintype "output"))
      (node (ref "R48") (pin "2") (pinfunction "2_2") (pintype "passive"))
      (node (ref "R52") (pin "1") (pinfunction "1_1") (pintype "passive"))
    )
    (net (code "100") (name "PT3_VS-") (class "Default")
      (node (ref "PT_123_IN") (pin "P$1") (pinfunction "SK_P$1") (pintype "passive"))
      (node (ref "PT_123_IN") (pin "P$7") (pinfunction "SK_P$7") (pintype "passive"))
      (node (ref "R33") (pin "2") (pinfunction "2_2") (pintype "passive"))
      (node (ref "R34") (pin "2") (pinfunction "2_2") (pintype "passive"))
    )
    (net (code "101") (name "PT4_PREC") (class "Default")
      (node (ref "IC4") (pin "4") (pinfunction "OUT_4") (pintype "output"))
      (node (ref "R50") (pin "2") (pinfunction "2_2") (pintype "passive"))
      (node (ref "R57") (pin "1") (pinfunction "1_1") (pintype "passive"))
    )
    (net (code "102") (name "PT4_VS-") (class "Default")
      (node (ref "R55") (pin "2") (pinfunction "2_2") (pintype "passive"))
      (node (ref "R56") (pin "2") (pinfunction "2_2") (pintype "passive"))
      (node (ref "TC_PT4_IN") (pin "P$11") (pinfunction "SK_P$11") (pintype "passive"))
      (node (ref "TC_PT4_IN") (pin "P$5") (pinfunction "SK_P$5") (pintype "passive"))
    )
    (net (code "103") (name "RELAY_NEGATIVE") (class "Default")
      (node (ref "D1") (pin "A") (pinfunction "A_A") (pintype "passive"))
      (node (ref "U$2") (pin "3") (pinfunction "D_3") (pintype "passive"))
      (node (ref "U$6") (pin "A1") (pinfunction "1_A1") (pintype "bidirectional"))
      (node (ref "U$6") (pin "B1") (pinfunction "1_B1") (pintype "bidirectional"))
    )
    (net (code "104") (name "SCLK") (class "Default")
      (node (ref "ADC1") (pin "13") (pinfunction "CLK_13") (pintype "bidirectional"))
      (node (ref "ADC2") (pin "13") (pinfunction "CLK_13") (pintype "bidirectional"))
      (node (ref "ADC3") (pin "13") (pinfunction "CLK_13") (pintype "bidirectional"))
      (node (ref "RPI_GPIO") (pin "23") (pinfunction "KL_23") (pintype "passive"))
    )
    (net (code "105") (name "SOLENOID_1_NEGATIVE") (class "Default")
      (node (ref "D2") (pin "A") (pinfunction "A_A") (pintype "passive"))
      (node (ref "U$3") (pin "3") (pinfunction "D_3") (pintype "passive"))
      (node (ref "U$6") (pin "A2") (pinfunction "2_A2") (pintype "bidirectional"))
      (node (ref "U$6") (pin "B2") (pinfunction "2_B2") (pintype "bidirectional"))
    )
    (net (code "106") (name "SOLENOID_2_NEGATIVE") (class "Default")
      (node (ref "D3") (pin "A") (pinfunction "A_A") (pintype "passive"))
      (node (ref "U$7") (pin "A1") (pinfunction "1_A1") (pintype "bidirectional"))
      (node (ref "U$7") (pin "B1") (pinfunction "1_B1") (pintype "bidirectional"))
      (node (ref "U$8") (pin "3") (pinfunction "D_3") (pintype "passive"))
    )
    (net (code "107") (name "SOLENOID_3_NEGATIVE") (class "Default")
      (node (ref "D4") (pin "A") (pinfunction "A_A") (pintype "passive"))
      (node (ref "U$7") (pin "A2") (pinfunction "2_A2") (pintype "bidirectional"))
      (node (ref "U$7") (pin "B2") (pinfunction "2_B2") (pintype "bidirectional"))
      (node (ref "U$9") (pin "3") (pinfunction "D_3") (pintype "passive"))
    )
    (net (code "108") (name "unconnected-(R10A-E-Pad1-3)") (class "Default")
      (node (ref "R10") (pin "1-3") (pinfunction "E_1-3") (pintype "passive"))
    )
    (net (code "109") (name "unconnected-(R10B-E-Pad2-3)") (class "Default")
      (node (ref "R10") (pin "2-3") (pinfunction "E_2-3") (pintype "passive"))
    )
    (net (code "110") (name "unconnected-(R13A-E-Pad1-3)") (class "Default")
      (node (ref "R13") (pin "1-3") (pinfunction "E_1-3") (pintype "passive"))
    )
    (net (code "111") (name "unconnected-(R13B-E-Pad2-3)") (class "Default")
      (node (ref "R13") (pin "2-3") (pinfunction "E_2-3") (pintype "passive"))
    )
    (net (code "112") (name "unconnected-(R18A-E-Pad1-3)") (class "Default")
      (node (ref "R18") (pin "1-3") (pinfunction "E_1-3") (pintype "passive"))
    )
    (net (code "113") (name "unconnected-(R18B-E-Pad2-3)") (class "Default")
      (node (ref "R18") (pin "2-3") (pinfunction "E_2-3") (pintype "passive"))
    )
    (net (code "114") (name "unconnected-(R22A-E-Pad1-3)") (class "Default")
      (node (ref "R22") (pin "1-3") (pinfunction "E_1-3") (pintype "passive"))
    )
    (net (code "115") (name "unconnected-(R22B-E-Pad2-3)") (class "Default")
      (node (ref "R22") (pin "2-3") (pinfunction "E_2-3") (pintype "passive"))
    )
    (net (code "116") (name "unconnected-(RPI_GPIOA-KL-Pad1)") (class "Default")
      (node (ref "RPI_GPIO") (pin "1") (pinfunction "KL_1") (pintype "passive"))
    )
    (net (code "117") (name "unconnected-(RPI_GPIOAA-KL-Pad33)") (class "Default")
      (node (ref "RPI_GPIO") (pin "33") (pinfunction "KL_33") (pintype "passive"))
    )
    (net (code "118") (name "unconnected-(RPI_GPIOAB-KL-Pad34)") (class "Default")
      (node (ref "RPI_GPIO") (pin "34") (pinfunction "KL_34") (pintype "passive"))
    )
    (net (code "119") (name "unconnected-(RPI_GPIOAC-KL-Pad35)") (class "Default")
      (node (ref "RPI_GPIO") (pin "35") (pinfunction "KL_35") (pintype "passive"))
    )
    (net (code "120") (name "unconnected-(RPI_GPIOAD-KL-Pad36)") (class "Default")
      (node (ref "RPI_GPIO") (pin "36") (pinfunction "KL_36") (pintype "passive"))
    )
    (net (code "121") (name "unconnected-(RPI_GPIOAE-KL-Pad37)") (class "Default")
      (node (ref "RPI_GPIO") (pin "37") (pinfunction "KL_37") (pintype "passive"))
    )
    (net (code "122") (name "unconnected-(RPI_GPIOAF-KL-Pad38)") (class "Default")
      (node (ref "RPI_GPIO") (pin "38") (pinfunction "KL_38") (pintype "passive"))
    )
    (net (code "123") (name "unconnected-(RPI_GPIOAG-KL-Pad39)") (class "Default")
      (node (ref "RPI_GPIO") (pin "39") (pinfunction "KL_39") (pintype "passive"))
    )
    (net (code "124") (name "unconnected-(RPI_GPIOAH-KL-Pad4)") (class "Default")
      (node (ref "RPI_GPIO") (pin "4") (pinfunction "KL_4") (pintype "passive"))
    )
    (net (code "125") (name "unconnected-(RPI_GPIOAI-KL-Pad40)") (class "Default")
      (node (ref "RPI_GPIO") (pin "40") (pinfunction "KL_40") (pintype "passive"))
    )
    (net (code "126") (name "unconnected-(RPI_GPIOAJ-KL-Pad5)") (class "Default")
      (node (ref "RPI_GPIO") (pin "5") (pinfunction "KL_5") (pintype "passive"))
    )
    (net (code "127") (name "unconnected-(RPI_GPIOAL-KL-Pad7)") (class "Default")
      (node (ref "RPI_GPIO") (pin "7") (pinfunction "KL_7") (pintype "passive"))
    )
    (net (code "128") (name "unconnected-(RPI_GPIOAM-KL-Pad8)") (class "Default")
      (node (ref "RPI_GPIO") (pin "8") (pinfunction "KL_8") (pintype "passive"))
    )
    (net (code "129") (name "unconnected-(RPI_GPIOAN-KL-Pad9)") (class "Default")
      (node (ref "RPI_GPIO") (pin "9") (pinfunction "KL_9") (pintype "passive"))
    )
    (net (code "130") (name "unconnected-(RPI_GPIOB-KL-Pad10)") (class "Default")
      (node (ref "RPI_GPIO") (pin "10") (pinfunction "KL_10") (pintype "passive"))
    )
    (net (code "131") (name "unconnected-(RPI_GPIOD-KL-Pad12)") (class "Default")
      (node (ref "RPI_GPIO") (pin "12") (pinfunction "KL_12") (pintype "passive"))
    )
    (net (code "132") (name "unconnected-(RPI_GPIOF-KL-Pad14)") (class "Default")
      (node (ref "RPI_GPIO") (pin "14") (pinfunction "KL_14") (pintype "passive"))
    )
    (net (code "133") (name "unconnected-(RPI_GPIOI-KL-Pad17)") (class "Default")
      (node (ref "RPI_GPIO") (pin "17") (pinfunction "KL_17") (pintype "passive"))
    )
    (net (code "134") (name "unconnected-(RPI_GPIOJ-KL-Pad18)") (class "Default")
      (node (ref "RPI_GPIO") (pin "18") (pinfunction "KL_18") (pintype "passive"))
    )
    (net (code "135") (name "unconnected-(RPI_GPIOM-KL-Pad20)") (class "Default")
      (node (ref "RPI_GPIO") (pin "20") (pinfunction "KL_20") (pintype "passive"))
    )
    (net (code "136") (name "unconnected-(RPI_GPIOR-KL-Pad25)") (class "Default")
      (node (ref "RPI_GPIO") (pin "25") (pinfunction "KL_25") (pintype "passive"))
    )
    (net (code "137") (name "unconnected-(RPI_GPIOT-KL-Pad27)") (class "Default")
      (node (ref "RPI_GPIO") (pin "27") (pinfunction "KL_27") (pintype "passive"))
    )
    (net (code "138") (name "unconnected-(RPI_GPIOU-KL-Pad28)") (class "Default")
      (node (ref "RPI_GPIO") (pin "28") (pinfunction "KL_28") (pintype "passive"))
    )
    (net (code "139") (name "unconnected-(RPI_GPIOV-KL-Pad29)") (class "Default")
      (node (ref "RPI_GPIO") (pin "29") (pinfunction "KL_29") (pintype "passive"))
    )
    (net (code "140") (name "unconnected-(RPI_GPIOW-KL-Pad3)") (class "Default")
      (node (ref "RPI_GPIO") (pin "3") (pinfunction "KL_3") (pintype "passive"))
    )
    (net (code "141") (name "unconnected-(RPI_GPIOX-KL-Pad30)") (class "Default")
      (node (ref "RPI_GPIO") (pin "30") (pinfunction "KL_30") (pintype "passive"))
    )
    (net (code "142") (name "unconnected-(RPI_GPIOY-KL-Pad31)") (class "Default")
      (node (ref "RPI_GPIO") (pin "31") (pinfunction "KL_31") (pintype "passive"))
    )
    (net (code "143") (name "unconnected-(RPI_GPIOZ-KL-Pad32)") (class "Default")
      (node (ref "RPI_GPIO") (pin "32") (pinfunction "KL_32") (pintype "passive"))
    )
    (net (code "144") (name "unconnected-(U2-VOCM-Pad2)") (class "Default")
      (node (ref "U2") (pin "2") (pinfunction "VOCM_2") (pintype "bidirectional"))
    )
    (net (code "145") (name "unconnected-(U3-VOCM-Pad2)") (class "Default")
      (node (ref "U3") (pin "2") (pinfunction "VOCM_2") (pintype "bidirectional"))
    )
    (net (code "146") (name "unconnected-(U4-VOCM-Pad2)") (class "Default")
      (node (ref "U4") (pin "2") (pinfunction "VOCM_2") (pintype "bidirectional"))
    )
    (net (code "147") (name "unconnected-(U5-VOCM-Pad2)") (class "Default")
      (node (ref "U5") (pin "2") (pinfunction "VOCM_2") (pintype "bidirectional"))
    )
    (net (code "148") (name "unconnected-(U6-S-Pad3)") (class "Default")
      (node (ref "U6") (pin "3") (pinfunction "S_3") (pintype "passive"))
    )
  )
)
